# ESP-RC-Car.net
KiCad netlist of a schematic drawn in Altium Designer
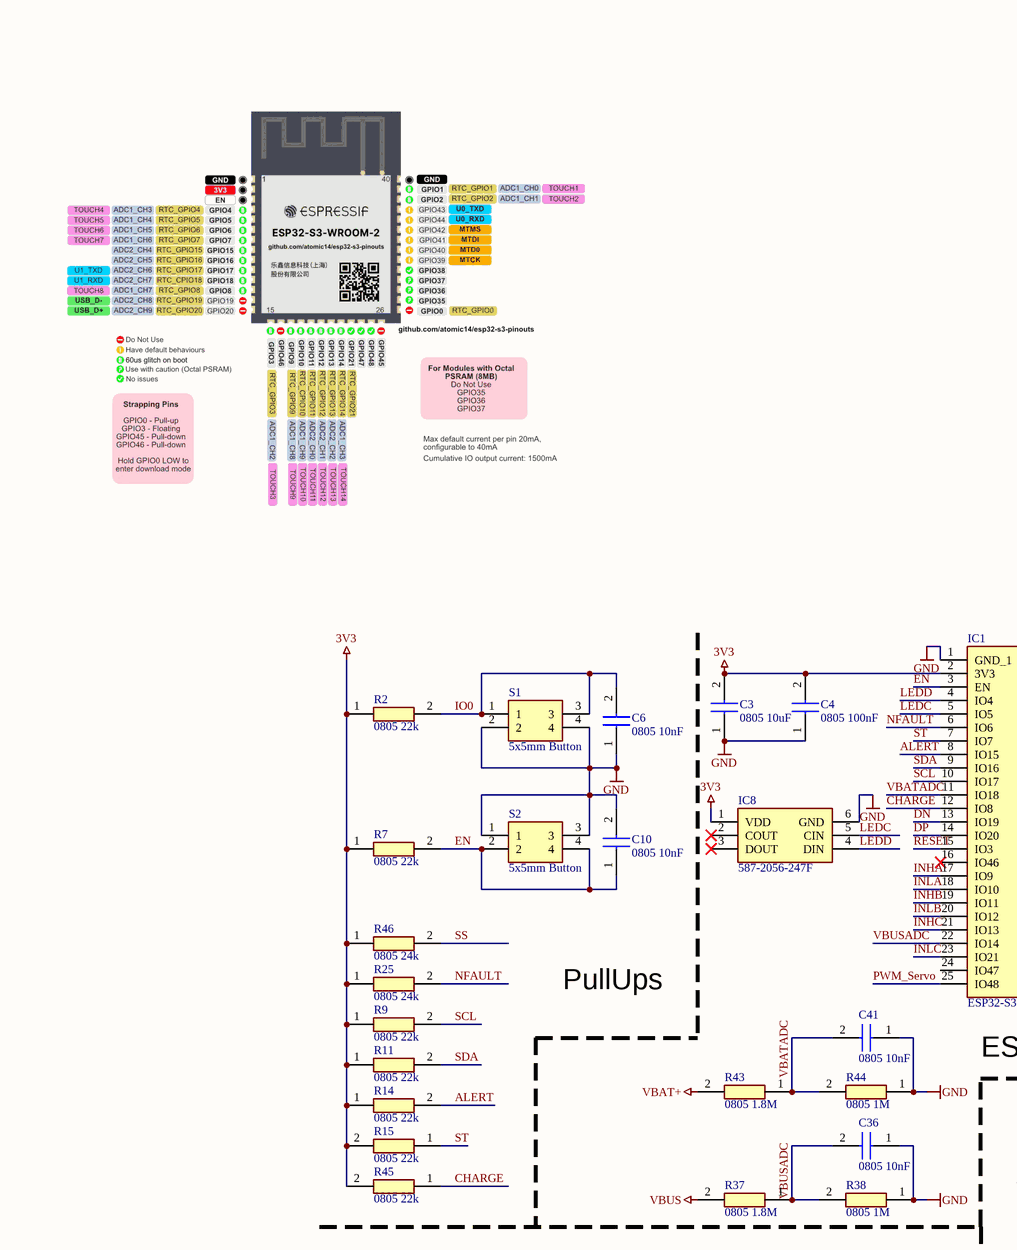
[diagram p0: ESP-RC-Car.SchDoc, top left]
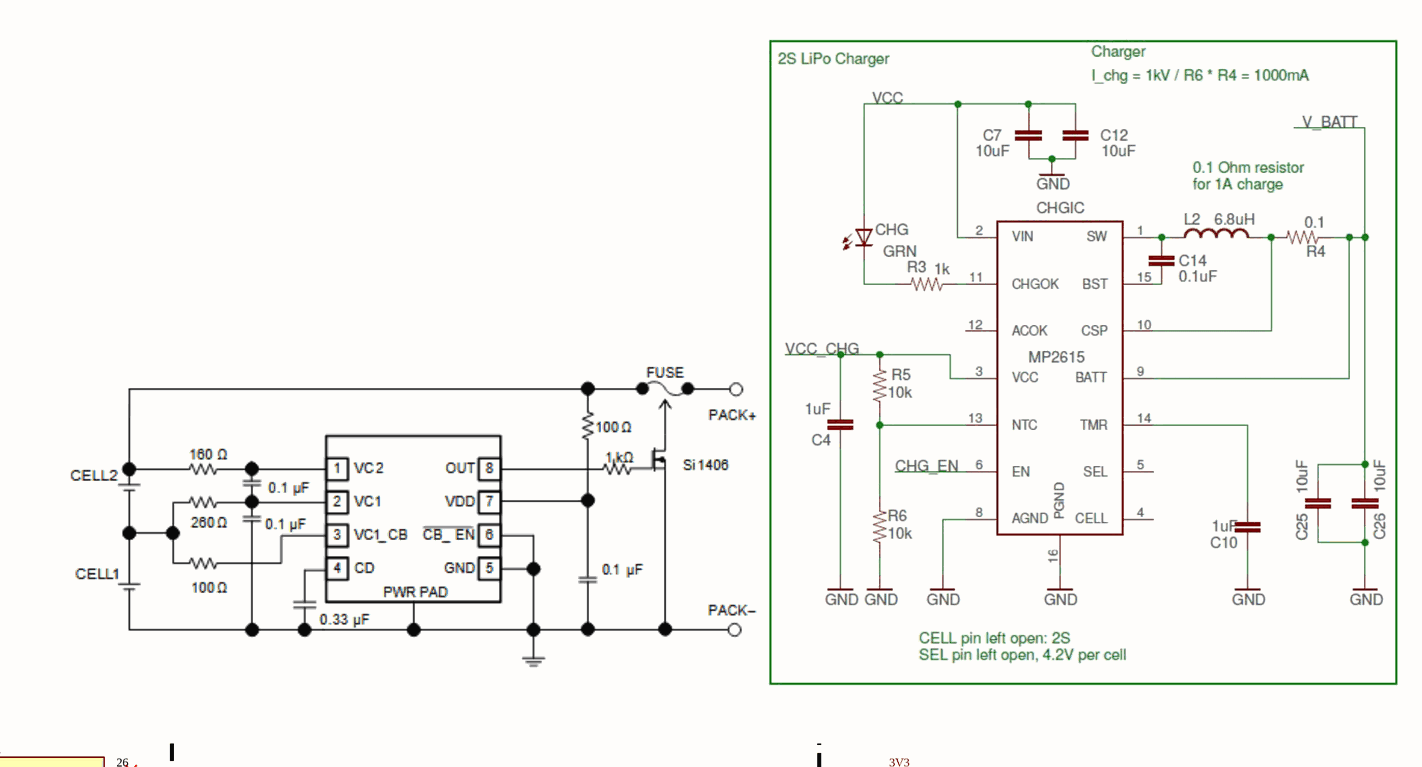
[diagram p1: ESP-RC-Car.SchDoc, top middle]
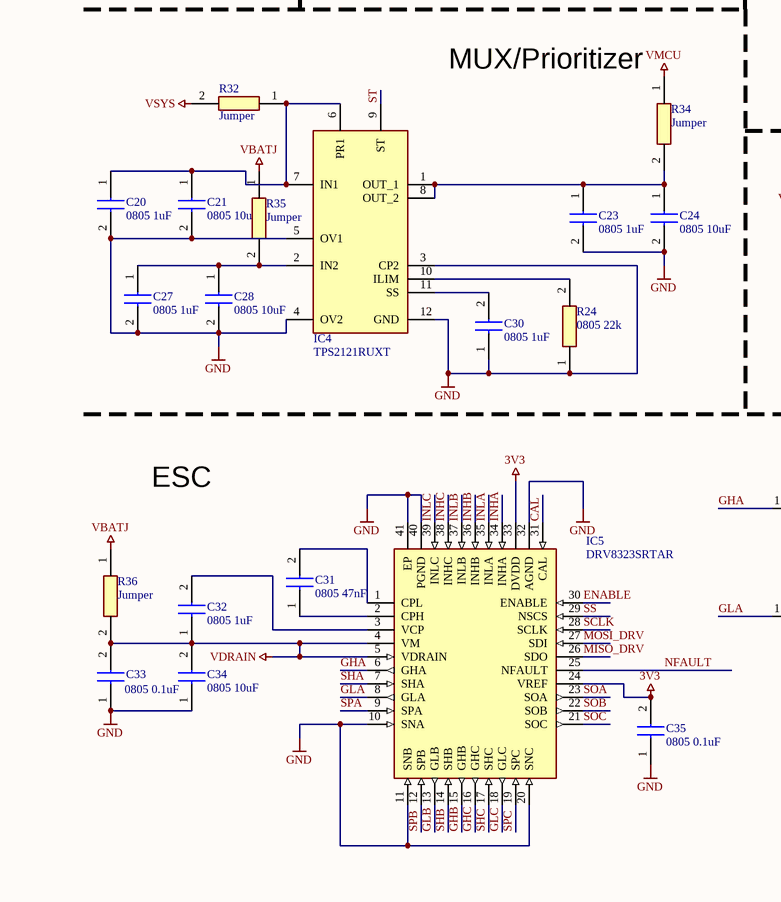
[diagram p2: ESP-RC-Car.SchDoc, bottom left]
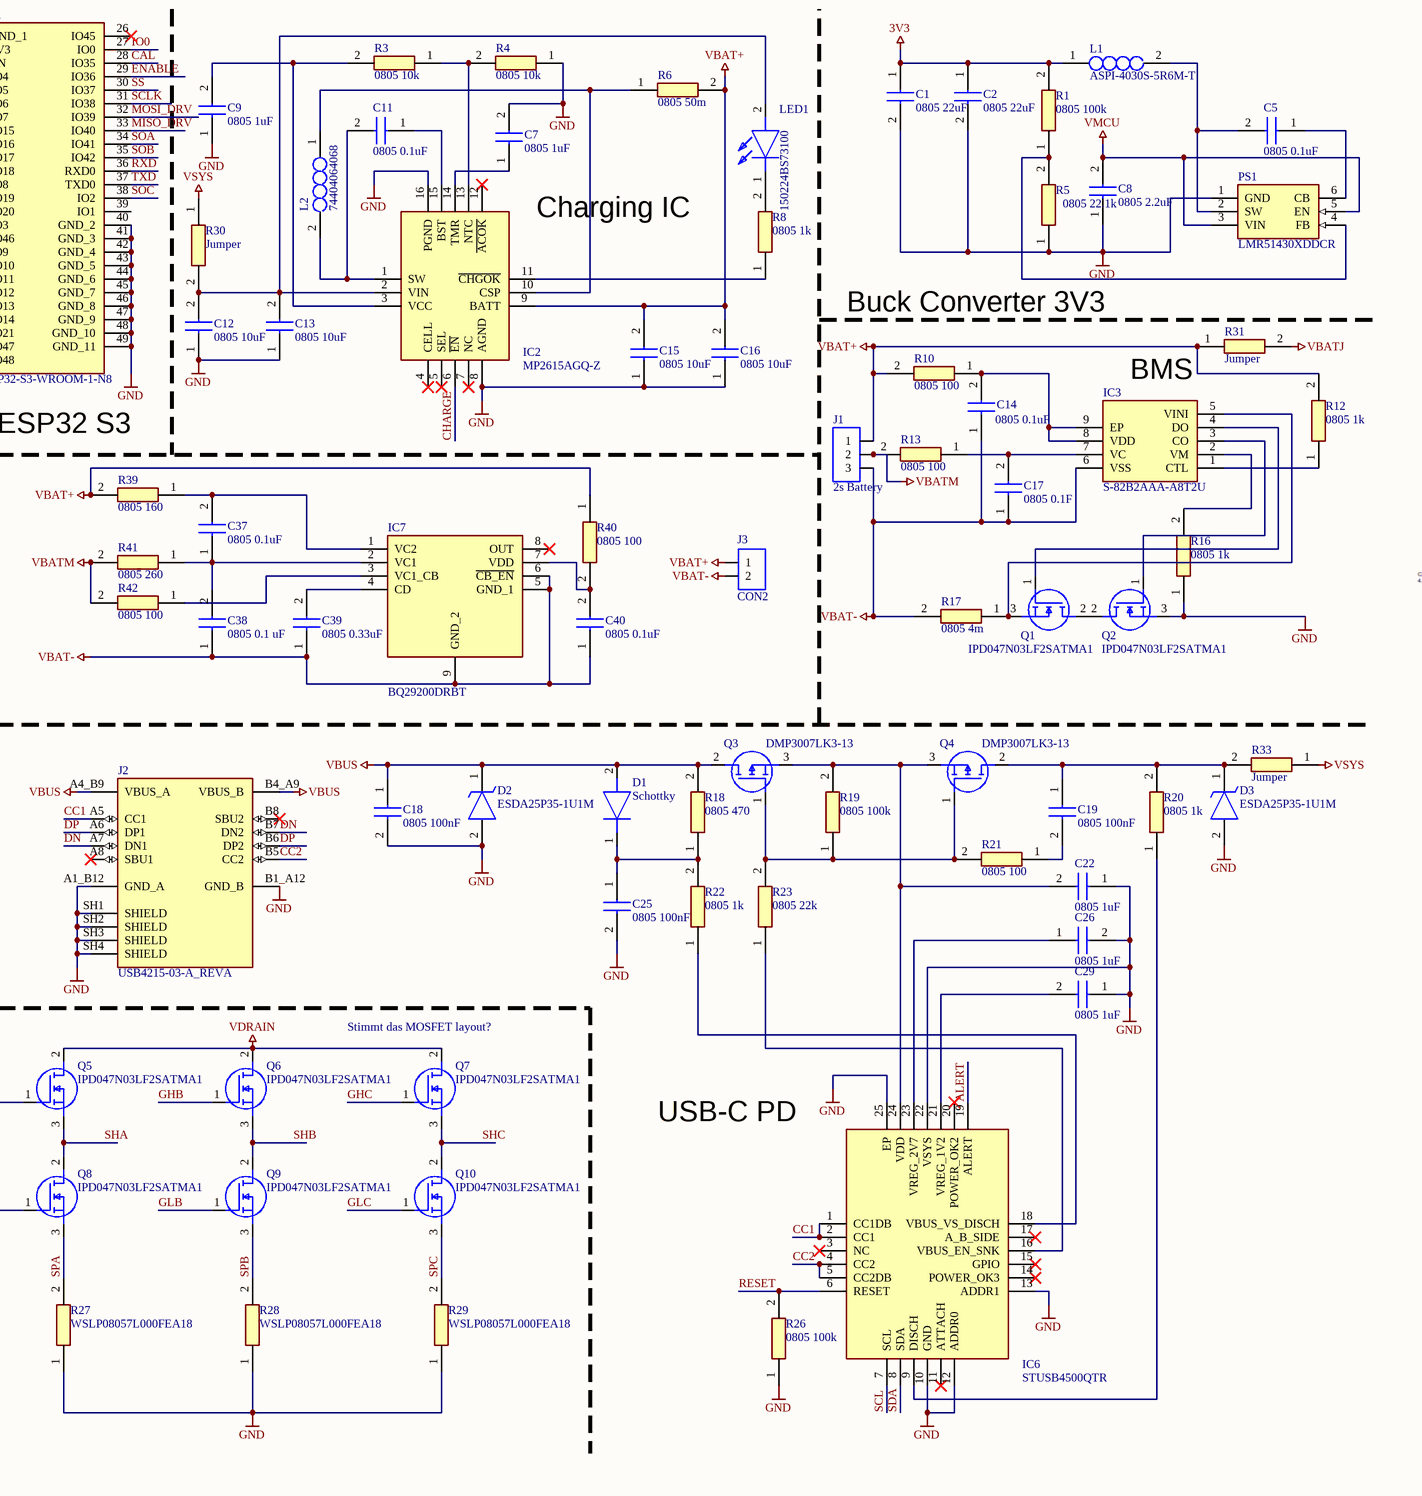
[diagram p3: ESP-RC-Car.SchDoc, bottom middle]
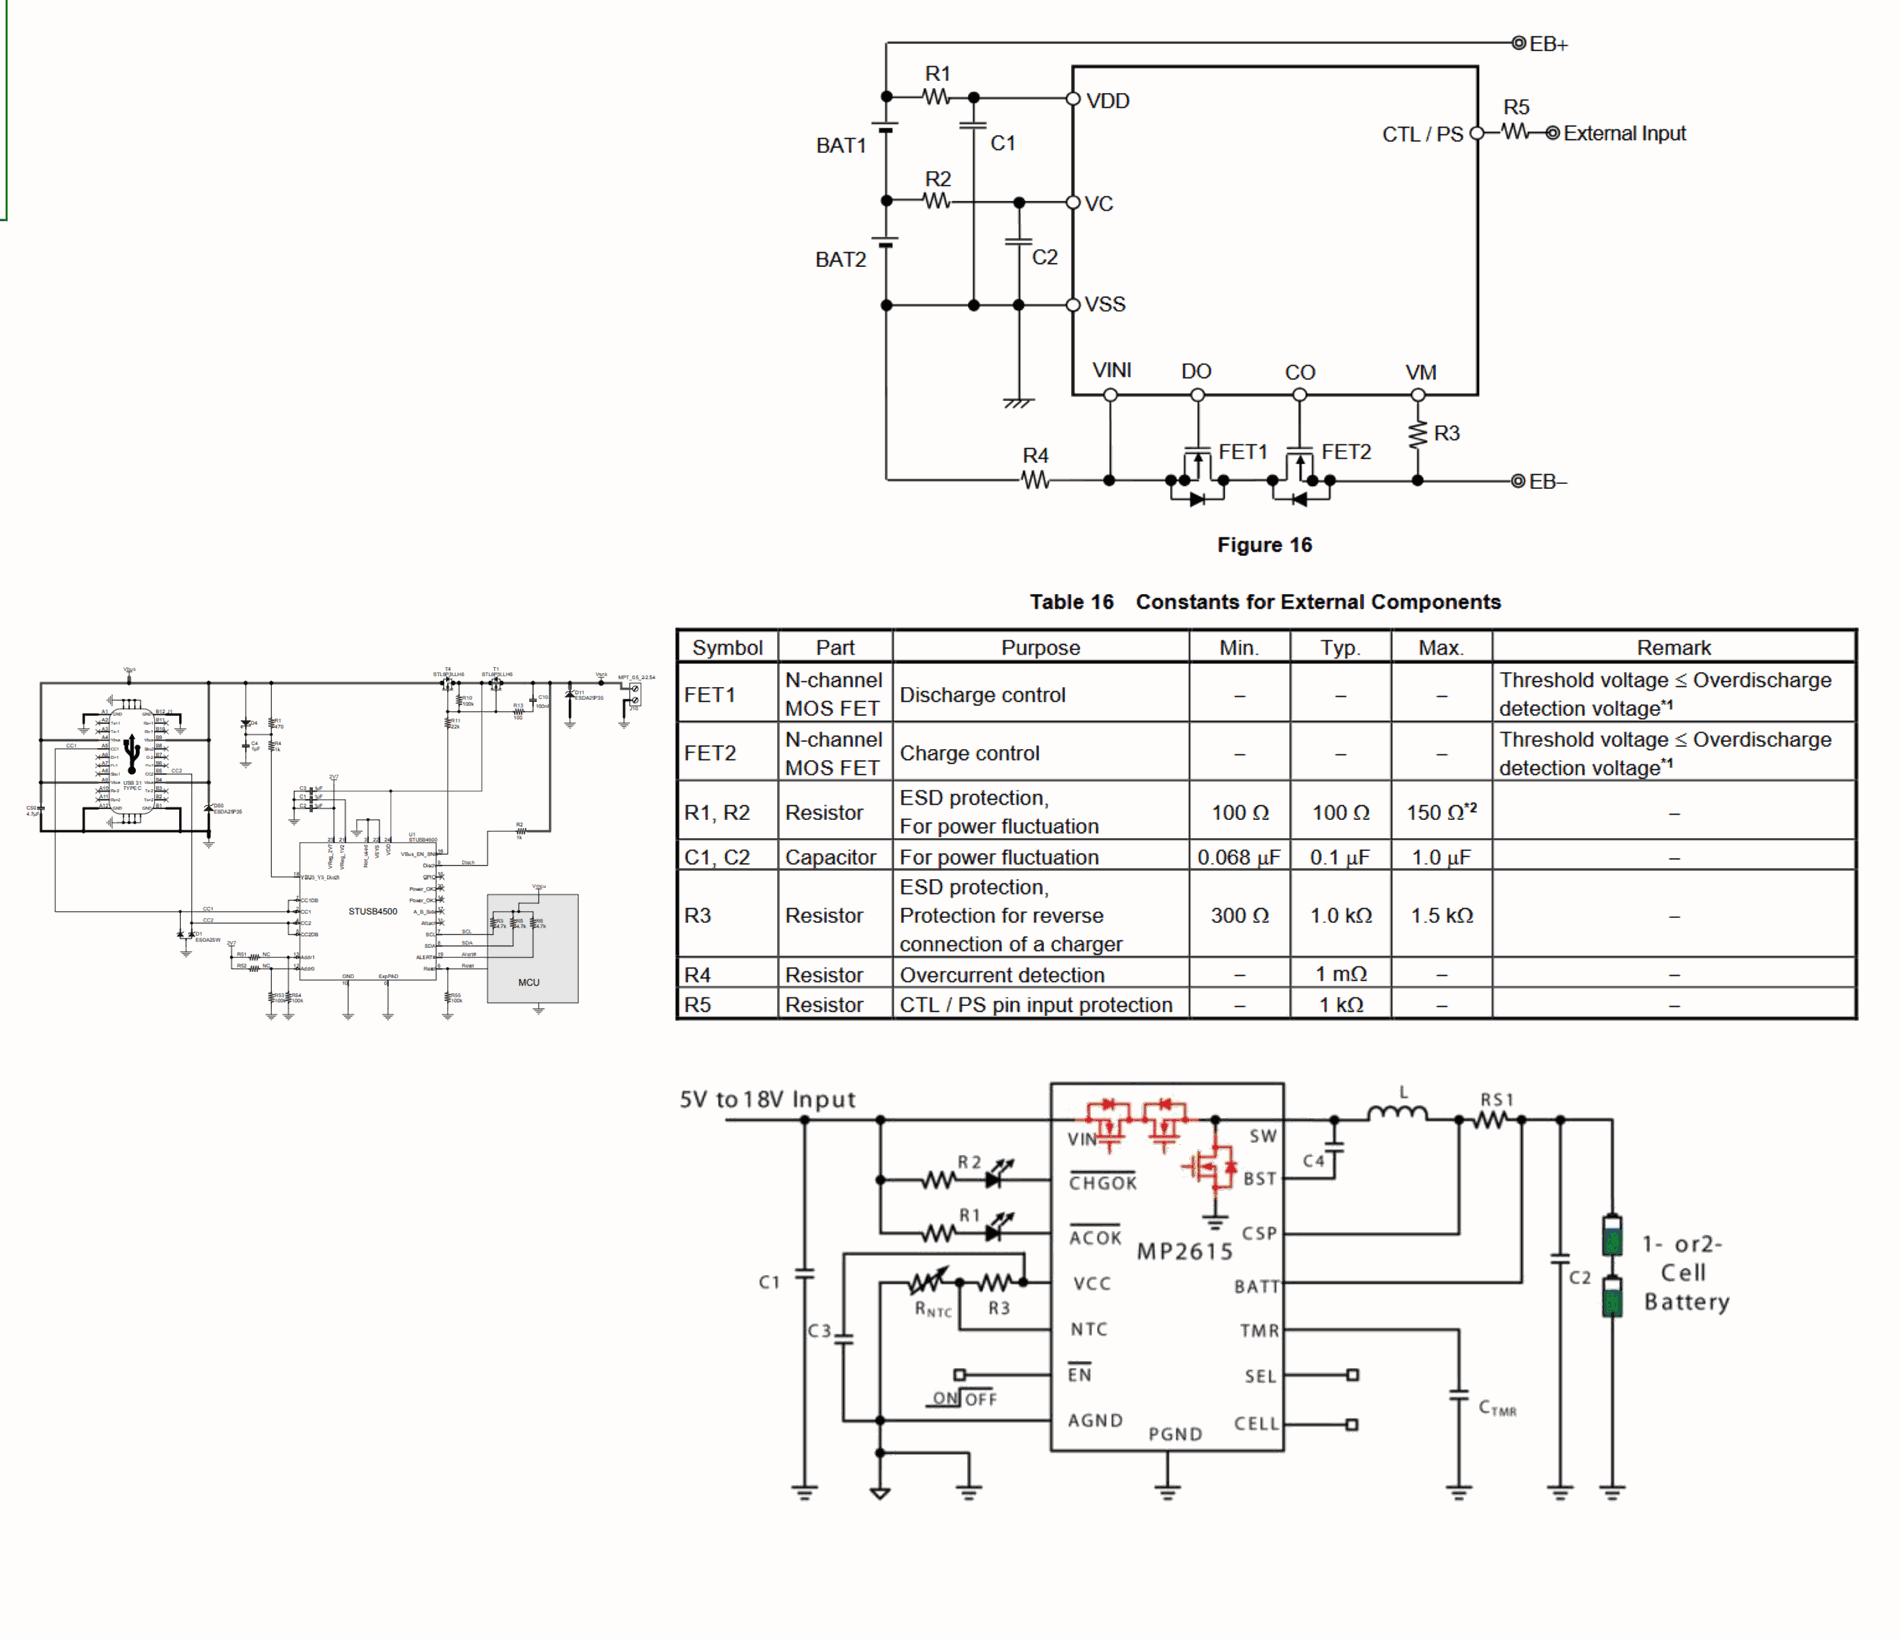
[diagram p4: ESP-RC-Car.SchDoc, bottom right]

(export (version "E")
  (design (tool "Eeschema 10.0.6"))
  (components
    (comp (ref "C1")
      (value "0805 22uF")
      (footprint "CAPC2012X94N")
      (description "Capacitor 25V")
      (fields
        (field (name "MANUFACTURER_PART_NUMBER") "08055A150JAT2A")
        (field (name "MOUSER PART NUMBER") "581-08055A150J")
      )
      (libsource (lib "*") (part "08055A150JAT2A"))
    )
    (comp (ref "C2")
      (value "0805 22uF")
      (footprint "CAPC2012X94N")
      (description "Capacitor 25V")
      (fields
        (field (name "MANUFACTURER_PART_NUMBER") "08055A150JAT2A")
        (field (name "MOUSER PART NUMBER") "581-08055A150J")
      )
      (libsource (lib "*") (part "08055A150JAT2A"))
    )
    (comp (ref "C3")
      (value "0805 10uF")
      (footprint "CAPC2012X94N")
      (description "Capacitor")
      (fields
        (field (name "MANUFACTURER_PART_NUMBER") "08055A150JAT2A")
        (field (name "MOUSER PART NUMBER") "581-08055A150J")
      )
      (libsource (lib "*") (part "08055A150JAT2A"))
    )
    (comp (ref "C4")
      (value "0805 100nF")
      (footprint "CAPC2012X94N")
      (description "Capacitor")
      (fields
        (field (name "MANUFACTURER_PART_NUMBER") "08055A150JAT2A")
        (field (name "MOUSER PART NUMBER") "581-08055A150J")
      )
      (libsource (lib "*") (part "08055A150JAT2A"))
    )
    (comp (ref "C5")
      (value "0805 0.1uF")
      (footprint "CAPC2012X94N")
      (description "Capacitor")
      (fields
        (field (name "MANUFACTURER_PART_NUMBER") "08055A150JAT2A")
        (field (name "MOUSER PART NUMBER") "581-08055A150J")
      )
      (libsource (lib "*") (part "08055A150JAT2A"))
    )
    (comp (ref "C6")
      (value "0805 10nF")
      (footprint "CAPC2012X94N")
      (description "Capacitor")
      (fields
        (field (name "MANUFACTURER_PART_NUMBER") "08055A150JAT2A")
        (field (name "MOUSER PART NUMBER") "581-08055A150J")
      )
      (libsource (lib "*") (part "08055A150JAT2A"))
    )
    (comp (ref "C7")
      (value "0805 1uF")
      (footprint "CAPC2012X94N")
      (description "Capacitor")
      (fields
        (field (name "MANUFACTURER_PART_NUMBER") "08055A150JAT2A")
        (field (name "MOUSER PART NUMBER") "581-08055A150J")
      )
      (libsource (lib "*") (part "08055A150JAT2A"))
    )
    (comp (ref "C8")
      (value "0805 2.2uF")
      (footprint "CAPC2012X94N")
      (description "Capacitor")
      (fields
        (field (name "MANUFACTURER_PART_NUMBER") "08055A150JAT2A")
        (field (name "MOUSER PART NUMBER") "581-08055A150J")
      )
      (libsource (lib "*") (part "08055A150JAT2A"))
    )
    (comp (ref "C9")
      (value "0805 1uF")
      (footprint "CAPC2012X94N")
      (description "Capacitor")
      (fields
        (field (name "MANUFACTURER_PART_NUMBER") "08055A150JAT2A")
        (field (name "MOUSER PART NUMBER") "581-08055A150J")
      )
      (libsource (lib "*") (part "08055A150JAT2A"))
    )
    (comp (ref "C10")
      (value "0805 10nF")
      (footprint "CAPC2012X94N")
      (description "Capacitor")
      (fields
        (field (name "MANUFACTURER_PART_NUMBER") "08055A150JAT2A")
        (field (name "MOUSER PART NUMBER") "581-08055A150J")
      )
      (libsource (lib "*") (part "08055A150JAT2A"))
    )
    (comp (ref "C11")
      (value "0805 0.1uF")
      (footprint "CAPC2012X94N")
      (description "Capacitor")
      (fields
        (field (name "MANUFACTURER_PART_NUMBER") "08055A150JAT2A")
        (field (name "MOUSER PART NUMBER") "581-08055A150J")
      )
      (libsource (lib "*") (part "08055A150JAT2A"))
    )
    (comp (ref "C12")
      (value "0805 10uF")
      (footprint "CAPC2012X94N")
      (description "Capacitor")
      (fields
        (field (name "MANUFACTURER_PART_NUMBER") "08055A150JAT2A")
        (field (name "MOUSER PART NUMBER") "581-08055A150J")
      )
      (libsource (lib "*") (part "08055A150JAT2A"))
    )
    (comp (ref "C13")
      (value "0805 10uF")
      (footprint "CAPC2012X94N")
      (description "Capacitor")
      (fields
        (field (name "MANUFACTURER_PART_NUMBER") "08055A150JAT2A")
        (field (name "MOUSER PART NUMBER") "581-08055A150J")
      )
      (libsource (lib "*") (part "08055A150JAT2A"))
    )
    (comp (ref "C14")
      (value "0805 0.1uF")
      (footprint "CAPC2012X94N")
      (description "Capacitor")
      (fields
        (field (name "MANUFACTURER_PART_NUMBER") "08055A150JAT2A")
        (field (name "MOUSER PART NUMBER") "581-08055A150J")
      )
      (libsource (lib "*") (part "08055A150JAT2A"))
    )
    (comp (ref "C15")
      (value "0805 10uF")
      (footprint "CAPC2012X94N")
      (description "Capacitor")
      (fields
        (field (name "MANUFACTURER_PART_NUMBER") "08055A150JAT2A")
        (field (name "MOUSER PART NUMBER") "581-08055A150J")
      )
      (libsource (lib "*") (part "08055A150JAT2A"))
    )
    (comp (ref "C16")
      (value "0805 10uF")
      (footprint "CAPC2012X94N")
      (description "Capacitor")
      (fields
        (field (name "MANUFACTURER_PART_NUMBER") "08055A150JAT2A")
        (field (name "MOUSER PART NUMBER") "581-08055A150J")
      )
      (libsource (lib "*") (part "08055A150JAT2A"))
    )
    (comp (ref "C17")
      (value "0805 0.1F")
      (footprint "CAPC2012X94N")
      (description "Capacitor")
      (fields
        (field (name "MANUFACTURER_PART_NUMBER") "08055A150JAT2A")
        (field (name "MOUSER PART NUMBER") "581-08055A150J")
      )
      (libsource (lib "*") (part "08055A150JAT2A"))
    )
    (comp (ref "C18")
      (value "0805 100nF")
      (footprint "CAPC2012X94N")
      (description "0805")
      (fields
        (field (name "MANUFACTURER_PART_NUMBER") "08055A150JAT2A")
        (field (name "MOUSER PART NUMBER") "581-08055A150J")
      )
      (libsource (lib "*") (part "08055A150JAT2A"))
    )
    (comp (ref "C19")
      (value "0805 100nF")
      (footprint "CAPC2012X94N")
      (description "0805")
      (fields
        (field (name "MANUFACTURER_PART_NUMBER") "08055A150JAT2A")
        (field (name "MOUSER PART NUMBER") "581-08055A150J")
      )
      (libsource (lib "*") (part "08055A150JAT2A"))
    )
    (comp (ref "C20")
      (value "0805 1uF")
      (footprint "CAPC2012X94N")
      (description "0805")
      (fields
        (field (name "MANUFACTURER_PART_NUMBER") "08055A150JAT2A")
        (field (name "MOUSER PART NUMBER") "581-08055A150J")
      )
      (libsource (lib "*") (part "08055A150JAT2A"))
    )
    (comp (ref "C21")
      (value "0805 10uF")
      (footprint "CAPC2012X94N")
      (description "0805")
      (fields
        (field (name "MANUFACTURER_PART_NUMBER") "08055A150JAT2A")
        (field (name "MOUSER PART NUMBER") "581-08055A150J")
      )
      (libsource (lib "*") (part "08055A150JAT2A"))
    )
    (comp (ref "C22")
      (value "0805 1uF")
      (footprint "CAPC2012X94N")
      (description "0805")
      (fields
        (field (name "MANUFACTURER_PART_NUMBER") "08055A150JAT2A")
        (field (name "MOUSER PART NUMBER") "581-08055A150J")
      )
      (libsource (lib "*") (part "08055A150JAT2A"))
    )
    (comp (ref "C23")
      (value "0805 1uF")
      (footprint "CAPC2012X94N")
      (description "0805")
      (fields
        (field (name "MANUFACTURER_PART_NUMBER") "08055A150JAT2A")
        (field (name "MOUSER PART NUMBER") "581-08055A150J")
      )
      (libsource (lib "*") (part "08055A150JAT2A"))
    )
    (comp (ref "C24")
      (value "0805 10uF")
      (footprint "CAPC2012X94N")
      (description "0805")
      (fields
        (field (name "MANUFACTURER_PART_NUMBER") "08055A150JAT2A")
        (field (name "MOUSER PART NUMBER") "581-08055A150J")
      )
      (libsource (lib "*") (part "08055A150JAT2A"))
    )
    (comp (ref "C25")
      (value "0805 100nF")
      (footprint "CAPC2012X94N")
      (description "0805")
      (fields
        (field (name "MANUFACTURER_PART_NUMBER") "08055A150JAT2A")
        (field (name "MOUSER PART NUMBER") "581-08055A150J")
      )
      (libsource (lib "*") (part "08055A150JAT2A"))
    )
    (comp (ref "C26")
      (value "0805 1uF")
      (footprint "CAPC2012X94N")
      (description "0805")
      (fields
        (field (name "MANUFACTURER_PART_NUMBER") "08055A150JAT2A")
        (field (name "MOUSER PART NUMBER") "581-08055A150J")
      )
      (libsource (lib "*") (part "08055A150JAT2A"))
    )
    (comp (ref "C27")
      (value "0805 1uF")
      (footprint "CAPC2012X94N")
      (description "0805")
      (fields
        (field (name "MANUFACTURER_PART_NUMBER") "08055A150JAT2A")
        (field (name "MOUSER PART NUMBER") "581-08055A150J")
      )
      (libsource (lib "*") (part "08055A150JAT2A"))
    )
    (comp (ref "C28")
      (value "0805 10uF")
      (footprint "CAPC2012X94N")
      (description "0805")
      (fields
        (field (name "MANUFACTURER_PART_NUMBER") "08055A150JAT2A")
        (field (name "MOUSER PART NUMBER") "581-08055A150J")
      )
      (libsource (lib "*") (part "08055A150JAT2A"))
    )
    (comp (ref "C29")
      (value "0805 1uF")
      (footprint "CAPC2012X94N")
      (description "0805")
      (fields
        (field (name "MANUFACTURER_PART_NUMBER") "08055A150JAT2A")
        (field (name "MOUSER PART NUMBER") "581-08055A150J")
      )
      (libsource (lib "*") (part "08055A150JAT2A"))
    )
    (comp (ref "C30")
      (value "0805 1uF")
      (footprint "CAPC2012X94N")
      (description "0805")
      (fields
        (field (name "MANUFACTURER_PART_NUMBER") "08055A150JAT2A")
        (field (name "MOUSER PART NUMBER") "581-08055A150J")
      )
      (libsource (lib "*") (part "08055A150JAT2A"))
    )
    (comp (ref "C31")
      (value "0805 47nF")
      (footprint "CAPC2012X94N")
      (description "0805")
      (fields
        (field (name "MANUFACTURER_PART_NUMBER") "08055A150JAT2A")
        (field (name "MOUSER PART NUMBER") "581-08055A150J")
      )
      (libsource (lib "*") (part "08055A150JAT2A"))
    )
    (comp (ref "C32")
      (value "0805 1uF")
      (footprint "CAPC2012X94N")
      (description "0805 16V X5R/X7R")
      (fields
        (field (name "MANUFACTURER_PART_NUMBER") "08055A150JAT2A")
        (field (name "MOUSER PART NUMBER") "581-08055A150J")
      )
      (libsource (lib "*") (part "08055A150JAT2A"))
    )
    (comp (ref "C33")
      (value "0805 0.1uF")
      (footprint "CAPC2012X94N")
      (description "0805 VM rated")
      (fields
        (field (name "MANUFACTURER_PART_NUMBER") "08055A150JAT2A")
        (field (name "MOUSER PART NUMBER") "581-08055A150J")
      )
      (libsource (lib "*") (part "08055A150JAT2A"))
    )
    (comp (ref "C34")
      (value "0805 10uF")
      (footprint "CAPC2012X94N")
      (description "0805")
      (fields
        (field (name "MANUFACTURER_PART_NUMBER") "08055A150JAT2A")
        (field (name "MOUSER PART NUMBER") "581-08055A150J")
      )
      (libsource (lib "*") (part "08055A150JAT2A"))
    )
    (comp (ref "C35")
      (value "0805 0.1uF")
      (footprint "CAPC2012X94N")
      (description "0805")
      (fields
        (field (name "MANUFACTURER_PART_NUMBER") "08055A150JAT2A")
        (field (name "MOUSER PART NUMBER") "581-08055A150J")
      )
      (libsource (lib "*") (part "08055A150JAT2A"))
    )
    (comp (ref "C36")
      (value "0805 10nF")
      (footprint "CAPC2012X94N")
      (description "Capacitor")
      (fields
        (field (name "MANUFACTURER_PART_NUMBER") "08055A150JAT2A")
        (field (name "MOUSER PART NUMBER") "581-08055A150J")
      )
      (libsource (lib "*") (part "08055A150JAT2A"))
    )
    (comp (ref "C37")
      (value "0805 0.1uF")
      (footprint "CAPC2012X94N")
      (description "Capacitor")
      (fields
        (field (name "MANUFACTURER_PART_NUMBER") "08055A150JAT2A")
        (field (name "MOUSER PART NUMBER") "581-08055A150J")
      )
      (libsource (lib "*") (part "08055A150JAT2A"))
    )
    (comp (ref "C38")
      (value "0805 0.1 uF")
      (footprint "CAPC2012X94N")
      (description "Capacitor")
      (fields
        (field (name "MANUFACTURER_PART_NUMBER") "08055A150JAT2A")
        (field (name "MOUSER PART NUMBER") "581-08055A150J")
      )
      (libsource (lib "*") (part "08055A150JAT2A"))
    )
    (comp (ref "C39")
      (value "0805 0.33uF")
      (footprint "CAPC2012X94N")
      (description "Capacitor")
      (fields
        (field (name "MANUFACTURER_PART_NUMBER") "08055A150JAT2A")
        (field (name "MOUSER PART NUMBER") "581-08055A150J")
      )
      (libsource (lib "*") (part "08055A150JAT2A"))
    )
    (comp (ref "C40")
      (value "0805 0.1uF")
      (footprint "CAPC2012X94N")
      (description "Capacitor")
      (fields
        (field (name "MANUFACTURER_PART_NUMBER") "08055A150JAT2A")
        (field (name "MOUSER PART NUMBER") "581-08055A150J")
      )
      (libsource (lib "*") (part "08055A150JAT2A"))
    )
    (comp (ref "C41")
      (value "0805 10nF")
      (footprint "CAPC2012X94N")
      (description "Capacitor")
      (fields
        (field (name "MANUFACTURER_PART_NUMBER") "08055A150JAT2A")
        (field (name "MOUSER PART NUMBER") "581-08055A150J")
      )
      (libsource (lib "*") (part "08055A150JAT2A"))
    )
    (comp (ref "D1")
      (value "Schottky")
      (footprint "SODFL3517X110N")
      (description "Schottky Diode")
      (fields (field (name "MANUFACTURER_PART_NUMBER") "PMEG3010ER"))
      (libsource (lib "*") (part "PMEG3010ER"))
    )
    (comp (ref "D2")
      (value "ESDA25P35-1U1M")
      (footprint "ESDA25P351U1M")
      (description "TVS Diode (Uni-directional)")
      (fields (field (name "MOUSER PART NUMBER") "511-ESDA25P35-1U1M"))
      (libsource (lib "*") (part "ESDA25P35-1U1M"))
    )
    (comp (ref "D3")
      (value "ESDA25P35-1U1M")
      (footprint "ESDA25P351U1M")
      (description "TVS Diode (Uni-directional)")
      (fields (field (name "MOUSER PART NUMBER") "511-ESDA25P35-1U1M"))
      (libsource (lib "*") (part "ESDA25P35-1U1M"))
    )
    (comp (ref "IC1")
      (value "ESP32-S3-WROOM-1-N8")
      (footprint "ESP32S3WROOM1N8R2")
      (description "Integrated Circuit")
      (fields (field (name "MOUSER PART NUMBER") "356-ESP32-S3WROOM1N8"))
      (libsource (lib "*") (part "ESP32-S3-WROOM-1-N8"))
    )
    (comp (ref "IC2")
      (value "MP2615AGQ-Z")
      (footprint "MP2615AGQZ")
      (description "Integrated Circuit")
      (fields (field (name "MOUSER PART NUMBER") "946-MP2615AGQ-Z"))
      (libsource (lib "*") (part "MP2615AGQ-Z"))
    )
    (comp (ref "IC3")
      (value "S-82B2AAA-A8T2U")
      (footprint "S82B2AAAA8T2U")
      (description "Integrated Circuit")
      (fields (field (name "MOUSER PART NUMBER") "628-S-82B2AAA-A8T2U"))
      (libsource (lib "*") (part "S-82B2AAA-A8T2U"))
    )
    (comp (ref "IC4")
      (value "TPS2121RUXT")
      (footprint "TPS2121RUXT")
      (description "Integrated Circuit")
      (fields (field (name "MOUSER PART NUMBER") "595-TPS2121RUXT"))
      (libsource (lib "*") (part "TPS2121RUXT"))
    )
    (comp (ref "IC5")
      (value "DRV8323SRTAR")
      (footprint "QFN50P600X600X80-41N-D")
      (description "Integrated Circuit")
      (fields (field (name "MOUSER PART NUMBER") "595-DRV8323SRTAR"))
      (libsource (lib "lib") (part "DRV8323SRTAR"))
    )
    (comp (ref "IC6")
      (value "STUSB4500QTR")
      (footprint "QFN50P400X400X100-25N-D")
      (description "Integrated Circuit")
      (fields (field (name "MOUSER PART NUMBER") "511-STUSB4500QTR"))
      (libsource (lib "*") (part "STUSB4500QTR"))
    )
    (comp (ref "IC7")
      (value "BQ29200DRBT")
      (footprint "SON65P300X300X100-9N-D")
      (description "Integrated Circuit")
      (fields (field (name "MOUSER PART NUMBER") "595-BQ29200DRBT"))
      (libsource (lib "*") (part "BQ29200DRBT"))
    )
    (comp (ref "IC8")
      (value "587-2056-247F")
      (footprint "lib:5872056247F")
      (description "Integrated Circuit")
      (libsource (lib "*") (part "587-2056-247F"))
    )
    (comp (ref "J1")
      (value "2s Battery")
      (footprint "Sip-3")
      (description "Stecker")
      (libsource (lib "lib") (part "CON3"))
    )
    (comp (ref "J2")
      (value "USB4215-03-A_REVA")
      (footprint "GCT_USB4215-03-A_REVA")
      (fields (field (name "MF") "Global Connector Technology") (field (name "MP") "USB4215-03-A"))
      (libsource (lib "lib") (part "USB4215-03-A_REVA"))
    )
    (comp (ref "J3")
      (value "CON2")
      (footprint "SIP-2")
      (description "Stecker")
      (libsource (lib "lib") (part "CON2"))
    )
    (comp (ref "L1")
      (value "ASPI-4030S-5R6M-T")
      (footprint "ASPI-4030S")
      (description "Inductor")
      (fields (field (name "MOUSER PART NUMBER") "815-ASPI-4030S-5R6MT"))
      (libsource (lib "*") (part "ASPI-4030S-5R6M-T"))
    )
    (comp (ref "L2")
      (value "74404064068")
      (footprint "INDPM6060X450N")
      (description "Inductor")
      (fields (field (name "MOUSER PART NUMBER") "710-74404064068"))
      (libsource (lib "*") (part "74404064068"))
    )
    (comp (ref "LED1")
      (value "150224BS73100")
      (footprint "150224BS73100")
      (description "LED")
      (fields (field (name "MOUSER PART NUMBER") "710-150224BS73100"))
      (libsource (lib "*") (part "150224BS73100"))
    )
    (comp (ref "PS1")
      (value "LMR51430XDDCR")
      (footprint "SOT95P280X110-6N")
      (description "Power Supply 500kHz")
      (fields (field (name "MOUSER PART NUMBER") "595-LMR51430XDDCR"))
      (libsource (lib "*") (part "LMR51430XDDCR"))
    )
    (comp (ref "Q1")
      (value "IPD047N03LF2SATMA1")
      (footprint "IPD047N03LF2SATMA1")
      (description "MOSFET (N-Channel)")
      (fields (field (name "MOUSER PART NUMBER") "726-IPD047N03LF2SATM"))
      (libsource (lib "*") (part "IPD047N03LF2SATMA1"))
    )
    (comp (ref "Q2")
      (value "IPD047N03LF2SATMA1")
      (footprint "IPD047N03LF2SATMA1")
      (description "MOSFET (N-Channel)")
      (fields (field (name "MOUSER PART NUMBER") "726-IPD047N03LF2SATM"))
      (libsource (lib "*") (part "IPD047N03LF2SATMA1"))
    )
    (comp (ref "Q3")
      (value "DMP3007LK3-13")
      (footprint "DMP3007LK313")
      (description "MOSFET (P-Channel)")
      (fields (field (name "MOUSER PART NUMBER") "621-DMP3007LK3-13"))
      (libsource (lib "*") (part "DMP3007LK3-13"))
    )
    (comp (ref "Q4")
      (value "DMP3007LK3-13")
      (footprint "DMP3007LK313")
      (description "MOSFET (P-Channel)")
      (fields (field (name "MOUSER PART NUMBER") "621-DMP3007LK3-13"))
      (libsource (lib "*") (part "DMP3007LK3-13"))
    )
    (comp (ref "Q5")
      (value "IPD047N03LF2SATMA1")
      (footprint "IPD047N03LF2SATMA1")
      (description "MOSFET (N-Channel)")
      (fields (field (name "MOUSER PART NUMBER") "726-IPD047N03LF2SATM"))
      (libsource (lib "*") (part "IPD047N03LF2SATMA1"))
    )
    (comp (ref "Q6")
      (value "IPD047N03LF2SATMA1")
      (footprint "IPD047N03LF2SATMA1")
      (description "MOSFET (N-Channel)")
      (fields (field (name "MOUSER PART NUMBER") "726-IPD047N03LF2SATM"))
      (libsource (lib "*") (part "IPD047N03LF2SATMA1"))
    )
    (comp (ref "Q7")
      (value "IPD047N03LF2SATMA1")
      (footprint "IPD047N03LF2SATMA1")
      (description "MOSFET (N-Channel)")
      (fields (field (name "MOUSER PART NUMBER") "726-IPD047N03LF2SATM"))
      (libsource (lib "*") (part "IPD047N03LF2SATMA1"))
    )
    (comp (ref "Q8")
      (value "IPD047N03LF2SATMA1")
      (footprint "IPD047N03LF2SATMA1")
      (description "MOSFET (N-Channel)")
      (fields (field (name "MOUSER PART NUMBER") "726-IPD047N03LF2SATM"))
      (libsource (lib "*") (part "IPD047N03LF2SATMA1"))
    )
    (comp (ref "Q9")
      (value "IPD047N03LF2SATMA1")
      (footprint "IPD047N03LF2SATMA1")
      (description "MOSFET (N-Channel)")
      (fields (field (name "MOUSER PART NUMBER") "726-IPD047N03LF2SATM"))
      (libsource (lib "*") (part "IPD047N03LF2SATMA1"))
    )
    (comp (ref "Q10")
      (value "IPD047N03LF2SATMA1")
      (footprint "IPD047N03LF2SATMA1")
      (description "MOSFET (N-Channel)")
      (fields (field (name "MOUSER PART NUMBER") "726-IPD047N03LF2SATM"))
      (libsource (lib "*") (part "IPD047N03LF2SATMA1"))
    )
    (comp (ref "R1")
      (value "0805 100k")
      (footprint "RESC2012X65N")
      (description "Resistor low tolerance")
      (fields (field (name "MANUFACTURER_PART_NUMBER") "CPF0805B102RE1"))
      (libsource (lib "") (part "CPF0805B102RE1_2"))
    )
    (comp (ref "R2")
      (value "0805 22k")
      (footprint "RESC2012X65N")
      (description "Resistor")
      (fields (field (name "MANUFACTURER_PART_NUMBER") "CPF0805B102RE1"))
      (libsource (lib "*") (part "CPF0805B102RE1"))
    )
    (comp (ref "R3")
      (value "0805 10k")
      (footprint "RESC2012X65N")
      (description "Resistor low tolerance")
      (fields (field (name "MANUFACTURER_PART_NUMBER") "CPF0805B102RE1"))
      (libsource (lib "") (part "CPF0805B102RE1_1"))
    )
    (comp (ref "R4")
      (value "0805 10k")
      (footprint "RESC2012X65N")
      (description "Resistor low tolerance")
      (fields (field (name "MANUFACTURER_PART_NUMBER") "CPF0805B102RE1"))
      (libsource (lib "") (part "CPF0805B102RE1_1"))
    )
    (comp (ref "R5")
      (value "0805 22.1k")
      (footprint "RESC2012X65N")
      (description "Resistor low tolerance")
      (fields (field (name "MANUFACTURER_PART_NUMBER") "CPF0805B102RE1"))
      (libsource (lib "") (part "CPF0805B102RE1_2"))
    )
    (comp (ref "R6")
      (value "0805 50m")
      (footprint "RESC2012X65N")
      (description "Resistor low tolerance")
      (fields (field (name "MANUFACTURER_PART_NUMBER") "CPF0805B102RE1"))
      (libsource (lib "*") (part "CPF0805B102RE1"))
    )
    (comp (ref "R7")
      (value "0805 22k")
      (footprint "RESC2012X65N")
      (description "Resistor")
      (fields (field (name "MANUFACTURER_PART_NUMBER") "CPF0805B102RE1"))
      (libsource (lib "*") (part "CPF0805B102RE1"))
    )
    (comp (ref "R8")
      (value "0805 1k")
      (footprint "RESC2012X65N")
      (description "Resistor low tolerance")
      (fields (field (name "MANUFACTURER_PART_NUMBER") "CPF0805B102RE1"))
      (libsource (lib "") (part "CPF0805B102RE1_2"))
    )
    (comp (ref "R9")
      (value "0805 22k")
      (footprint "RESC2012X65N")
      (description "Resistor")
      (fields (field (name "MANUFACTURER_PART_NUMBER") "CPF0805B102RE1"))
      (libsource (lib "*") (part "CPF0805B102RE1"))
    )
    (comp (ref "R10")
      (value "0805 100")
      (footprint "RESC2012X65N")
      (description "Resistor low tolerance")
      (fields (field (name "MANUFACTURER_PART_NUMBER") "CPF0805B102RE1"))
      (libsource (lib "") (part "CPF0805B102RE1_1"))
    )
    (comp (ref "R11")
      (value "0805 22k")
      (footprint "RESC2012X65N")
      (description "Resistor")
      (fields (field (name "MANUFACTURER_PART_NUMBER") "CPF0805B102RE1"))
      (libsource (lib "*") (part "CPF0805B102RE1"))
    )
    (comp (ref "R12")
      (value "0805 1k")
      (footprint "RESC2012X65N")
      (description "Resistor low tolerance")
      (fields (field (name "MANUFACTURER_PART_NUMBER") "CPF0805B102RE1"))
      (libsource (lib "") (part "CPF0805B102RE1_2"))
    )
    (comp (ref "R13")
      (value "0805 100")
      (footprint "RESC2012X65N")
      (description "Resistor low tolerance")
      (fields (field (name "MANUFACTURER_PART_NUMBER") "CPF0805B102RE1"))
      (libsource (lib "") (part "CPF0805B102RE1_1"))
    )
    (comp (ref "R14")
      (value "0805 22k")
      (footprint "RESC2012X65N")
      (description "Resistor")
      (fields (field (name "MANUFACTURER_PART_NUMBER") "CPF0805B102RE1"))
      (libsource (lib "*") (part "CPF0805B102RE1"))
    )
    (comp (ref "R15")
      (value "0805 22k")
      (footprint "RESC2012X65N")
      (description "Resistor")
      (fields (field (name "MANUFACTURER_PART_NUMBER") "CPF0805B102RE1"))
      (libsource (lib "") (part "CPF0805B102RE1_1"))
    )
    (comp (ref "R16")
      (value "0805 1k")
      (footprint "RESC2012X65N")
      (description "Resistor low tolerance")
      (fields (field (name "MANUFACTURER_PART_NUMBER") "CPF0805B102RE1"))
      (libsource (lib "") (part "CPF0805B102RE1_2"))
    )
    (comp (ref "R17")
      (value "0805 4m")
      (footprint "RESC2012X65N")
      (description "Resistor low tolerance")
      (fields (field (name "MANUFACTURER_PART_NUMBER") "CPF0805B102RE1"))
      (libsource (lib "") (part "CPF0805B102RE1_1"))
    )
    (comp (ref "R18")
      (value "0805 470")
      (footprint "RESC2012X65N")
      (description "Resistor")
      (fields (field (name "MANUFACTURER_PART_NUMBER") "CPF0805B102RE1"))
      (libsource (lib "") (part "CPF0805B102RE1_2"))
    )
    (comp (ref "R19")
      (value "0805 100k")
      (footprint "RESC2012X65N")
      (description "Resistor")
      (fields (field (name "MANUFACTURER_PART_NUMBER") "CPF0805B102RE1"))
      (libsource (lib "") (part "CPF0805B102RE1_2"))
    )
    (comp (ref "R20")
      (value "0805 1k")
      (footprint "RESC2012X65N")
      (description "Resistor")
      (fields (field (name "MANUFACTURER_PART_NUMBER") "CPF0805B102RE1"))
      (libsource (lib "") (part "CPF0805B102RE1_2"))
    )
    (comp (ref "R21")
      (value "0805 100")
      (footprint "RESC2012X65N")
      (description "Resistor")
      (fields (field (name "MANUFACTURER_PART_NUMBER") "CPF0805B102RE1"))
      (libsource (lib "") (part "CPF0805B102RE1_1"))
    )
    (comp (ref "R22")
      (value "0805 1k")
      (footprint "RESC2012X65N")
      (description "Resistor")
      (fields (field (name "MANUFACTURER_PART_NUMBER") "CPF0805B102RE1"))
      (libsource (lib "") (part "CPF0805B102RE1_2"))
    )
    (comp (ref "R23")
      (value "0805 22k")
      (footprint "RESC2012X65N")
      (description "Resistor")
      (fields (field (name "MANUFACTURER_PART_NUMBER") "CPF0805B102RE1"))
      (libsource (lib "") (part "CPF0805B102RE1_2"))
    )
    (comp (ref "R24")
      (value "0805 22k")
      (footprint "RESC2012X65N")
      (description "Resistor")
      (fields (field (name "MANUFACTURER_PART_NUMBER") "CPF0805B102RE1"))
      (libsource (lib "") (part "CPF0805B102RE1_2"))
    )
    (comp (ref "R25")
      (value "0805 24k")
      (footprint "RESC2012X65N")
      (description "Resistor")
      (fields (field (name "MANUFACTURER_PART_NUMBER") "CPF0805B102RE1"))
      (libsource (lib "*") (part "CPF0805B102RE1"))
    )
    (comp (ref "R26")
      (value "0805 100k")
      (footprint "RESC2012X65N")
      (description "Resistor")
      (fields (field (name "MANUFACTURER_PART_NUMBER") "CPF0805B102RE1"))
      (libsource (lib "") (part "CPF0805B102RE1_2"))
    )
    (comp (ref "R27")
      (value "WSLP08057L000FEA18")
      (footprint "RESC2013X58N")
      (description "Resistor")
      (fields (field (name "MOUSER PART NUMBER") "71-WSLP08057L000FEA1"))
      (libsource (lib "*") (part "WSLP08057L000FEA18"))
    )
    (comp (ref "R28")
      (value "WSLP08057L000FEA18")
      (footprint "RESC2013X58N")
      (description "Resistor")
      (fields (field (name "MOUSER PART NUMBER") "71-WSLP08057L000FEA1"))
      (libsource (lib "*") (part "WSLP08057L000FEA18"))
    )
    (comp (ref "R29")
      (value "WSLP08057L000FEA18")
      (footprint "RESC2013X58N")
      (description "Resistor")
      (fields (field (name "MOUSER PART NUMBER") "71-WSLP08057L000FEA1"))
      (libsource (lib "*") (part "WSLP08057L000FEA18"))
    )
    (comp (ref "R30")
      (value "Jumper")
      (footprint "Solder Jumper 5A")
      (description "Resistor")
      (fields (field (name "MANUFACTURER_PART_NUMBER") "CPF0805B102RE1"))
      (libsource (lib "") (part "CPF0805B102RE1_3"))
    )
    (comp (ref "R31")
      (value "Jumper")
      (footprint "Solder Jumper 9A")
      (description "Resistor")
      (fields (field (name "MANUFACTURER_PART_NUMBER") "CPF0805B102RE1"))
      (libsource (lib "*") (part "CPF0805B102RE1"))
    )
    (comp (ref "R32")
      (value "Jumper")
      (footprint "Solder Jumper 5A")
      (description "Resistor")
      (fields (field (name "MANUFACTURER_PART_NUMBER") "CPF0805B102RE1"))
      (libsource (lib "") (part "CPF0805B102RE1_1"))
    )
    (comp (ref "R33")
      (value "Jumper")
      (footprint "Solder Jumper 5A")
      (description "Resistor")
      (fields (field (name "MANUFACTURER_PART_NUMBER") "CPF0805B102RE1"))
      (libsource (lib "") (part "CPF0805B102RE1_1"))
    )
    (comp (ref "R34")
      (value "Jumper")
      (footprint "Solder Jumper 5A")
      (description "Resistor")
      (fields (field (name "MANUFACTURER_PART_NUMBER") "CPF0805B102RE1"))
      (libsource (lib "") (part "CPF0805B102RE1_3"))
    )
    (comp (ref "R35")
      (value "Jumper")
      (footprint "Solder Jumper 5A")
      (description "Resistor")
      (fields (field (name "MANUFACTURER_PART_NUMBER") "CPF0805B102RE1"))
      (libsource (lib "") (part "CPF0805B102RE1_3"))
    )
    (comp (ref "R36")
      (value "Jumper")
      (footprint "Solder Jumper 9A")
      (description "Resistor")
      (fields (field (name "MANUFACTURER_PART_NUMBER") "CPF0805B102RE1"))
      (libsource (lib "") (part "CPF0805B102RE1_3"))
    )
    (comp (ref "R37")
      (value "0805 1.8M")
      (footprint "RESC2012X65N")
      (description "Resistor")
      (fields (field (name "MANUFACTURER_PART_NUMBER") "CPF0805B102RE1"))
      (libsource (lib "") (part "CPF0805B102RE1_1"))
    )
    (comp (ref "R38")
      (value "0805 1M")
      (footprint "RESC2012X65N")
      (description "Resistor")
      (fields (field (name "MANUFACTURER_PART_NUMBER") "CPF0805B102RE1"))
      (libsource (lib "") (part "CPF0805B102RE1_1"))
    )
    (comp (ref "R39")
      (value "0805 160")
      (footprint "RESC2012X65N")
      (description "Resistor low tolerance")
      (fields (field (name "MANUFACTURER_PART_NUMBER") "CPF0805B102RE1"))
      (libsource (lib "") (part "CPF0805B102RE1_1"))
    )
    (comp (ref "R40")
      (value "0805 100")
      (footprint "RESC2012X65N")
      (description "Resistor low tolerance")
      (fields (field (name "MANUFACTURER_PART_NUMBER") "CPF0805B102RE1"))
      (libsource (lib "") (part "CPF0805B102RE1_3"))
    )
    (comp (ref "R41")
      (value "0805 260")
      (footprint "RESC2012X65N")
      (description "Resistor low tolerance")
      (fields (field (name "MANUFACTURER_PART_NUMBER") "CPF0805B102RE1"))
      (libsource (lib "") (part "CPF0805B102RE1_1"))
    )
    (comp (ref "R42")
      (value "0805 100")
      (footprint "RESC2012X65N")
      (description "Resistor low tolerance")
      (fields (field (name "MANUFACTURER_PART_NUMBER") "CPF0805B102RE1"))
      (libsource (lib "") (part "CPF0805B102RE1_1"))
    )
    (comp (ref "R43")
      (value "0805 1.8M")
      (footprint "RESC2012X65N")
      (description "Resistor")
      (fields (field (name "MANUFACTURER_PART_NUMBER") "CPF0805B102RE1"))
      (libsource (lib "") (part "CPF0805B102RE1_1"))
    )
    (comp (ref "R44")
      (value "0805 1M")
      (footprint "RESC2012X65N")
      (description "Resistor")
      (fields (field (name "MANUFACTURER_PART_NUMBER") "CPF0805B102RE1"))
      (libsource (lib "") (part "CPF0805B102RE1_1"))
    )
    (comp (ref "R45")
      (value "0805 22k")
      (footprint "RESC2012X65N")
      (description "Resistor")
      (fields (field (name "MANUFACTURER_PART_NUMBER") "CPF0805B102RE1"))
      (libsource (lib "") (part "CPF0805B102RE1_1"))
    )
    (comp (ref "R46")
      (value "0805 24k")
      (footprint "RESC2012X65N")
      (description "Resistor")
      (fields (field (name "MANUFACTURER_PART_NUMBER") "CPF0805B102RE1"))
      (libsource (lib "*") (part "CPF0805B102RE1"))
    )
    (comp (ref "S1")
      (value "5x5mm Button")
      (footprint "430182070816")
      (description "Switch")
      (fields
        (field (name "MANUFACTURER_PART_NUMBER") "430182050816")
        (field (name "MOUSER PART NUMBER") "710-430182050816")
      )
      (libsource (lib "*") (part "430182050816"))
    )
    (comp (ref "S2")
      (value "5x5mm Button")
      (footprint "430182070816")
      (description "Switch")
      (fields
        (field (name "MANUFACTURER_PART_NUMBER") "430182050816")
        (field (name "MOUSER PART NUMBER") "710-430182050816")
      )
      (libsource (lib "*") (part "430182050816"))
    )
  )
  (nets
    (net (code "1") (name "/ALERT") (class "Default")
      (node (ref "IC1") (pin "8") (pinfunction "IO15_8") (pintype "passive"))
      (node (ref "IC6") (pin "19") (pinfunction "ALERT_19") (pintype "passive"))
      (node (ref "R14") (pin "2") (pinfunction "2_2") (pintype "passive"))
    )
    (net (code "2") (name "/CAL") (class "Default")
      (node (ref "IC1") (pin "28") (pinfunction "IO35_28") (pintype "passive"))
      (node (ref "IC5") (pin "31") (pinfunction "CAL_31") (pintype "input"))
    )
    (net (code "3") (name "/CC1") (class "Default")
      (node (ref "IC6") (pin "1") (pinfunction "CC1DB_1") (pintype "passive"))
      (node (ref "IC6") (pin "2") (pinfunction "CC1_2") (pintype "passive"))
      (node (ref "J2") (pin "A5") (pinfunction "CC1_A5") (pintype "bidirectional"))
    )
    (net (code "4") (name "/CC2") (class "Default")
      (node (ref "IC6") (pin "4") (pinfunction "CC2_4") (pintype "passive"))
      (node (ref "IC6") (pin "5") (pinfunction "CC2DB_5") (pintype "passive"))
      (node (ref "J2") (pin "B5") (pinfunction "CC2_B5") (pintype "bidirectional"))
    )
    (net (code "5") (name "/CHARGE") (class "Default")
      (node (ref "IC1") (pin "12") (pinfunction "IO8_12") (pintype "passive"))
      (node (ref "IC2") (pin "6") (pinfunction "~{EN}_6") (pintype "passive"))
      (node (ref "R45") (pin "1") (pinfunction "1_1") (pintype "passive"))
    )
    (net (code "6") (name "/DN") (class "Default")
      (node (ref "IC1") (pin "13") (pinfunction "IO19_13") (pintype "passive"))
      (node (ref "J2") (pin "A7") (pinfunction "DN1_A7") (pintype "bidirectional"))
      (node (ref "J2") (pin "B7") (pinfunction "DN2_B7") (pintype "bidirectional"))
    )
    (net (code "7") (name "/DP") (class "Default")
      (node (ref "IC1") (pin "14") (pinfunction "IO20_14") (pintype "passive"))
      (node (ref "J2") (pin "A6") (pinfunction "DP1_A6") (pintype "bidirectional"))
      (node (ref "J2") (pin "B6") (pinfunction "DP2_B6") (pintype "bidirectional"))
    )
    (net (code "8") (name "/EN") (class "Default")
      (node (ref "C10") (pin "1") (pinfunction "1_1") (pintype "passive"))
      (node (ref "IC1") (pin "3") (pinfunction "EN_3") (pintype "passive"))
      (node (ref "R7") (pin "2") (pinfunction "2_2") (pintype "passive"))
      (node (ref "S2") (pin "2") (pinfunction "2_2") (pintype "passive"))
      (node (ref "S2") (pin "4") (pinfunction "4_4") (pintype "passive"))
    )
    (net (code "9") (name "/ENABLE") (class "Default")
      (node (ref "IC1") (pin "29") (pinfunction "IO36_29") (pintype "passive"))
      (node (ref "IC5") (pin "30") (pinfunction "ENABLE_30") (pintype "input"))
    )
    (net (code "10") (name "/GHA") (class "Default")
      (node (ref "IC5") (pin "6") (pinfunction "GHA_6") (pintype "output"))
      (node (ref "Q5") (pin "1") (pinfunction "G_1") (pintype "passive"))
    )
    (net (code "11") (name "/GHB") (class "Default")
      (node (ref "IC5") (pin "15") (pinfunction "GHB_15") (pintype "output"))
      (node (ref "Q6") (pin "1") (pinfunction "G_1") (pintype "passive"))
    )
    (net (code "12") (name "/GHC") (class "Default")
      (node (ref "IC5") (pin "16") (pinfunction "GHC_16") (pintype "output"))
      (node (ref "Q7") (pin "1") (pinfunction "G_1") (pintype "passive"))
    )
    (net (code "13") (name "/GLA") (class "Default")
      (node (ref "IC5") (pin "8") (pinfunction "GLA_8") (pintype "output"))
      (node (ref "Q8") (pin "1") (pinfunction "G_1") (pintype "passive"))
    )
    (net (code "14") (name "/GLB") (class "Default")
      (node (ref "IC5") (pin "13") (pinfunction "GLB_13") (pintype "output"))
      (node (ref "Q9") (pin "1") (pinfunction "G_1") (pintype "passive"))
    )
    (net (code "15") (name "/GLC") (class "Default")
      (node (ref "IC5") (pin "18") (pinfunction "GLC_18") (pintype "output"))
      (node (ref "Q10") (pin "1") (pinfunction "G_1") (pintype "passive"))
    )
    (net (code "16") (name "/INHA") (class "Default")
      (node (ref "IC1") (pin "17") (pinfunction "IO9_17") (pintype "passive"))
      (node (ref "IC5") (pin "34") (pinfunction "INHA_34") (pintype "input"))
    )
    (net (code "17") (name "/INHB") (class "Default")
      (node (ref "IC1") (pin "19") (pinfunction "IO11_19") (pintype "passive"))
      (node (ref "IC5") (pin "36") (pinfunction "INHB_36") (pintype "input"))
    )
    (net (code "18") (name "/INHC") (class "Default")
      (node (ref "IC1") (pin "21") (pinfunction "IO13_21") (pintype "passive"))
      (node (ref "IC5") (pin "38") (pinfunction "INHC_38") (pintype "input"))
    )
    (net (code "19") (name "/INLA") (class "Default")
      (node (ref "IC1") (pin "18") (pinfunction "IO10_18") (pintype "passive"))
      (node (ref "IC5") (pin "35") (pinfunction "INLA_35") (pintype "input"))
    )
    (net (code "20") (name "/INLB") (class "Default")
      (node (ref "IC1") (pin "20") (pinfunction "IO12_20") (pintype "passive"))
      (node (ref "IC5") (pin "37") (pinfunction "INLB_37") (pintype "input"))
    )
    (net (code "21") (name "/INLC") (class "Default")
      (node (ref "IC1") (pin "23") (pinfunction "IO21_23") (pintype "passive"))
      (node (ref "IC5") (pin "39") (pinfunction "INLC_39") (pintype "input"))
    )
    (net (code "22") (name "/IO0") (class "Default")
      (node (ref "C6") (pin "2") (pinfunction "2_2") (pintype "passive"))
      (node (ref "IC1") (pin "27") (pinfunction "IO0_27") (pintype "passive"))
      (node (ref "R2") (pin "2") (pinfunction "2_2") (pintype "passive"))
      (node (ref "S1") (pin "1") (pinfunction "1_1") (pintype "passive"))
      (node (ref "S1") (pin "3") (pinfunction "3_3") (pintype "passive"))
    )
    (net (code "23") (name "/LEDC") (class "Default")
      (node (ref "IC1") (pin "5") (pinfunction "IO5_5") (pintype "passive"))
      (node (ref "IC8") (pin "5") (pinfunction "CIN_5") (pintype "passive"))
    )
    (net (code "24") (name "/LEDD") (class "Default")
      (node (ref "IC1") (pin "4") (pinfunction "IO4_4") (pintype "passive"))
      (node (ref "IC8") (pin "4") (pinfunction "DIN_4") (pintype "passive"))
    )
    (net (code "25") (name "/MISO_DRV") (class "Default")
      (node (ref "IC1") (pin "33") (pinfunction "IO40_33") (pintype "passive"))
      (node (ref "IC5") (pin "26") (pinfunction "SDO_26") (pintype "passive"))
    )
    (net (code "26") (name "/MOSI_DRV") (class "Default")
      (node (ref "IC1") (pin "32") (pinfunction "IO39_32") (pintype "passive"))
      (node (ref "IC5") (pin "27") (pinfunction "SDI_27") (pintype "input"))
    )
    (net (code "27") (name "/NFAULT") (class "Default")
      (node (ref "IC1") (pin "6") (pinfunction "IO6_6") (pintype "passive"))
      (node (ref "IC5") (pin "25") (pinfunction "NFAULT_25") (pintype "passive"))
      (node (ref "R25") (pin "2") (pinfunction "2_2") (pintype "passive"))
    )
    (net (code "28") (name "/PWM_Servo") (class "Default")
      (node (ref "IC1") (pin "25") (pinfunction "IO48_25") (pintype "passive"))
    )
    (net (code "29") (name "/RESET") (class "Default")
      (node (ref "IC1") (pin "15") (pinfunction "IO3_15") (pintype "passive"))
      (node (ref "IC6") (pin "6") (pinfunction "RESET_6") (pintype "passive"))
      (node (ref "R26") (pin "2") (pinfunction "2_2") (pintype "passive"))
    )
    (net (code "30") (name "/RXD") (class "Default")
      (node (ref "IC1") (pin "36") (pinfunction "RXD0_36") (pintype "passive"))
    )
    (net (code "31") (name "/SCL") (class "Default")
      (node (ref "IC1") (pin "10") (pinfunction "IO17_10") (pintype "passive"))
      (node (ref "IC6") (pin "7") (pinfunction "SCL_7") (pintype "passive"))
      (node (ref "R9") (pin "2") (pinfunction "2_2") (pintype "passive"))
    )
    (net (code "32") (name "/SCLK") (class "Default")
      (node (ref "IC1") (pin "31") (pinfunction "IO38_31") (pintype "passive"))
      (node (ref "IC5") (pin "28") (pinfunction "SCLK_28") (pintype "input"))
    )
    (net (code "33") (name "/SDA") (class "Default")
      (node (ref "IC1") (pin "9") (pinfunction "IO16_9") (pintype "passive"))
      (node (ref "IC6") (pin "8") (pinfunction "SDA_8") (pintype "passive"))
      (node (ref "R11") (pin "2") (pinfunction "2_2") (pintype "passive"))
    )
    (net (code "34") (name "/SHA") (class "Default")
      (node (ref "IC5") (pin "7") (pinfunction "SHA_7") (pintype "input"))
      (node (ref "Q5") (pin "3") (pinfunction "S_3") (pintype "passive"))
      (node (ref "Q8") (pin "2") (pinfunction "D_2") (pintype "passive"))
    )
    (net (code "35") (name "/SHB") (class "Default")
      (node (ref "IC5") (pin "14") (pinfunction "SHB_14") (pintype "input"))
      (node (ref "Q6") (pin "3") (pinfunction "S_3") (pintype "passive"))
      (node (ref "Q9") (pin "2") (pinfunction "D_2") (pintype "passive"))
    )
    (net (code "36") (name "/SHC") (class "Default")
      (node (ref "IC5") (pin "17") (pinfunction "SHC_17") (pintype "input"))
      (node (ref "Q10") (pin "2") (pinfunction "D_2") (pintype "passive"))
      (node (ref "Q7") (pin "3") (pinfunction "S_3") (pintype "passive"))
    )
    (net (code "37") (name "/SOA") (class "Default")
      (node (ref "IC1") (pin "34") (pinfunction "IO41_34") (pintype "passive"))
      (node (ref "IC5") (pin "23") (pinfunction "SOA_23") (pintype "output"))
    )
    (net (code "38") (name "/SOB") (class "Default")
      (node (ref "IC1") (pin "35") (pinfunction "IO42_35") (pintype "passive"))
      (node (ref "IC5") (pin "22") (pinfunction "SOB_22") (pintype "output"))
    )
    (net (code "39") (name "/SOC") (class "Default")
      (node (ref "IC1") (pin "38") (pinfunction "IO2_38") (pintype "passive"))
      (node (ref "IC5") (pin "21") (pinfunction "SOC_21") (pintype "output"))
    )
    (net (code "40") (name "/SPA") (class "Default")
      (node (ref "IC5") (pin "9") (pinfunction "SPA_9") (pintype "input"))
      (node (ref "Q8") (pin "3") (pinfunction "S_3") (pintype "passive"))
      (node (ref "R27") (pin "2") (pinfunction "2_2") (pintype "passive"))
    )
    (net (code "41") (name "/SPB") (class "Default")
      (node (ref "IC5") (pin "12") (pinfunction "SPB_12") (pintype "input"))
      (node (ref "Q9") (pin "3") (pinfunction "S_3") (pintype "passive"))
      (node (ref "R28") (pin "2") (pinfunction "2_2") (pintype "passive"))
    )
    (net (code "42") (name "/SPC") (class "Default")
      (node (ref "IC5") (pin "19") (pinfunction "SPC_19") (pintype "input"))
      (node (ref "Q10") (pin "3") (pinfunction "S_3") (pintype "passive"))
      (node (ref "R29") (pin "2") (pinfunction "2_2") (pintype "passive"))
    )
    (net (code "43") (name "/SS") (class "Default")
      (node (ref "IC1") (pin "30") (pinfunction "IO37_30") (pintype "passive"))
      (node (ref "IC5") (pin "29") (pinfunction "NSCS_29") (pintype "input"))
      (node (ref "R46") (pin "2") (pinfunction "2_2") (pintype "passive"))
    )
    (net (code "44") (name "/ST") (class "Default")
      (node (ref "IC1") (pin "7") (pinfunction "IO7_7") (pintype "passive"))
      (node (ref "IC4") (pin "9") (pinfunction "ST_9") (pintype "passive"))
      (node (ref "R15") (pin "1") (pinfunction "1_1") (pintype "passive"))
    )
    (net (code "45") (name "/TXD") (class "Default")
      (node (ref "IC1") (pin "37") (pinfunction "TXD0_37") (pintype "passive"))
    )
    (net (code "46") (name "/VBATADC") (class "Default")
      (node (ref "C41") (pin "2") (pinfunction "2_2") (pintype "passive"))
      (node (ref "IC1") (pin "11") (pinfunction "IO18_11") (pintype "passive"))
      (node (ref "R43") (pin "1") (pinfunction "1_1") (pintype "passive"))
      (node (ref "R44") (pin "2") (pinfunction "2_2") (pintype "passive"))
    )
    (net (code "47") (name "/VBUSADC") (class "Default")
      (node (ref "C36") (pin "2") (pinfunction "2_2") (pintype "passive"))
      (node (ref "IC1") (pin "22") (pinfunction "IO14_22") (pintype "passive"))
      (node (ref "R37") (pin "1") (pinfunction "1_1") (pintype "passive"))
      (node (ref "R38") (pin "2") (pinfunction "2_2") (pintype "passive"))
    )
    (net (code "48") (name "3V3") (class "Default")
      (node (ref "C1") (pin "1") (pinfunction "1_1") (pintype "passive"))
      (node (ref "C2") (pin "1") (pinfunction "1_1") (pintype "passive"))
      (node (ref "C3") (pin "2") (pinfunction "2_2") (pintype "passive"))
      (node (ref "C35") (pin "2") (pinfunction "2_2") (pintype "passive"))
      (node (ref "C4") (pin "2") (pinfunction "2_2") (pintype "passive"))
      (node (ref "IC1") (pin "2") (pinfunction "3V3_2") (pintype "passive"))
      (node (ref "IC5") (pin "24") (pinfunction "VREF_24") (pintype "power_in"))
      (node (ref "IC5") (pin "33") (pinfunction "DVDD_33") (pintype "power_in"))
      (node (ref "IC8") (pin "1") (pinfunction "VDD_1") (pintype "passive"))
      (node (ref "L1") (pin "1") (pinfunction "1_1") (pintype "passive"))
      (node (ref "R1") (pin "2") (pinfunction "2_2") (pintype "passive"))
      (node (ref "R11") (pin "1") (pinfunction "1_1") (pintype "passive"))
      (node (ref "R14") (pin "1") (pinfunction "1_1") (pintype "passive"))
      (node (ref "R15") (pin "2") (pinfunction "2_2") (pintype "passive"))
      (node (ref "R2") (pin "1") (pinfunction "1_1") (pintype "passive"))
      (node (ref "R25") (pin "1") (pinfunction "1_1") (pintype "passive"))
      (node (ref "R45") (pin "2") (pinfunction "2_2") (pintype "passive"))
      (node (ref "R46") (pin "1") (pinfunction "1_1") (pintype "passive"))
      (node (ref "R7") (pin "1") (pinfunction "1_1") (pintype "passive"))
      (node (ref "R9") (pin "1") (pinfunction "1_1") (pintype "passive"))
    )
    (net (code "49") (name "GND") (class "Default")
      (node (ref "C1") (pin "2") (pinfunction "2_2") (pintype "passive"))
      (node (ref "C10") (pin "2") (pinfunction "2_2") (pintype "passive"))
      (node (ref "C12") (pin "1") (pinfunction "1_1") (pintype "passive"))
      (node (ref "C13") (pin "1") (pinfunction "1_1") (pintype "passive"))
      (node (ref "C15") (pin "1") (pinfunction "1_1") (pintype "passive"))
      (node (ref "C16") (pin "1") (pinfunction "1_1") (pintype "passive"))
      (node (ref "C18") (pin "2") (pinfunction "2_2") (pintype "passive"))
      (node (ref "C2") (pin "2") (pinfunction "2_2") (pintype "passive"))
      (node (ref "C20") (pin "2") (pinfunction "2_2") (pintype "passive"))
      (node (ref "C21") (pin "2") (pinfunction "2_2") (pintype "passive"))
      (node (ref "C22") (pin "1") (pinfunction "1_1") (pintype "passive"))
      (node (ref "C23") (pin "2") (pinfunction "2_2") (pintype "passive"))
      (node (ref "C24") (pin "2") (pinfunction "2_2") (pintype "passive"))
      (node (ref "C25") (pin "2") (pinfunction "2_2") (pintype "passive"))
      (node (ref "C26") (pin "2") (pinfunction "2_2") (pintype "passive"))
      (node (ref "C27") (pin "2") (pinfunction "2_2") (pintype "passive"))
      (node (ref "C28") (pin "2") (pinfunction "2_2") (pintype "passive"))
      (node (ref "C29") (pin "1") (pinfunction "1_1") (pintype "passive"))
      (node (ref "C3") (pin "1") (pinfunction "1_1") (pintype "passive"))
      (node (ref "C30") (pin "1") (pinfunction "1_1") (pintype "passive"))
      (node (ref "C33") (pin "1") (pinfunction "1_1") (pintype "passive"))
      (node (ref "C34") (pin "1") (pinfunction "1_1") (pintype "passive"))
      (node (ref "C35") (pin "1") (pinfunction "1_1") (pintype "passive"))
      (node (ref "C36") (pin "1") (pinfunction "1_1") (pintype "passive"))
      (node (ref "C4") (pin "1") (pinfunction "1_1") (pintype "passive"))
      (node (ref "C41") (pin "1") (pinfunction "1_1") (pintype "passive"))
      (node (ref "C6") (pin "1") (pinfunction "1_1") (pintype "passive"))
      (node (ref "C7") (pin "2") (pinfunction "2_2") (pintype "passive"))
      (node (ref "C8") (pin "1") (pinfunction "1_1") (pintype "passive"))
      (node (ref "C9") (pin "1") (pinfunction "1_1") (pintype "passive"))
      (node (ref "D2") (pin "2") (pinfunction "A_2") (pintype "passive"))
      (node (ref "D3") (pin "2") (pinfunction "A_2") (pintype "passive"))
      (node (ref "IC1") (pin "1") (pinfunction "GND_1_1") (pintype "passive"))
      (node (ref "IC1") (pin "40") (pinfunction "GND_2_40") (pintype "passive"))
      (node (ref "IC1") (pin "41") (pinfunction "GND_3_41") (pintype "passive"))
      (node (ref "IC1") (pin "42") (pinfunction "GND_4_42") (pintype "passive"))
      (node (ref "IC1") (pin "43") (pinfunction "GND_5_43") (pintype "passive"))
      (node (ref "IC1") (pin "44") (pinfunction "GND_6_44") (pintype "passive"))
      (node (ref "IC1") (pin "45") (pinfunction "GND_7_45") (pintype "passive"))
      (node (ref "IC1") (pin "46") (pinfunction "GND_8_46") (pintype "passive"))
      (node (ref "IC1") (pin "47") (pinfunction "GND_9_47") (pintype "passive"))
      (node (ref "IC1") (pin "48") (pinfunction "GND_10_48") (pintype "passive"))
      (node (ref "IC1") (pin "49") (pinfunction "GND_11_49") (pintype "passive"))
      (node (ref "IC2") (pin "16") (pinfunction "PGND_16") (pintype "passive"))
      (node (ref "IC2") (pin "8") (pinfunction "AGND_8") (pintype "passive"))
      (node (ref "IC4") (pin "12") (pinfunction "GND_12") (pintype "passive"))
      (node (ref "IC4") (pin "3") (pinfunction "CP2_3") (pintype "passive"))
      (node (ref "IC4") (pin "4") (pinfunction "OV2_4") (pintype "passive"))
      (node (ref "IC4") (pin "5") (pinfunction "OV1_5") (pintype "passive"))
      (node (ref "IC5") (pin "10") (pinfunction "SNA_10") (pintype "input"))
      (node (ref "IC5") (pin "11") (pinfunction "SNB_11") (pintype "input"))
      (node (ref "IC5") (pin "20") (pinfunction "SNC_20") (pintype "input"))
      (node (ref "IC5") (pin "32") (pinfunction "AGND_32") (pintype "power_in"))
      (node (ref "IC5") (pin "40") (pinfunction "PGND_40") (pintype "power_in"))
      (node (ref "IC5") (pin "41") (pinfunction "EP_41") (pintype "power_in"))
      (node (ref "IC6") (pin "10") (pinfunction "GND_10") (pintype "passive"))
      (node (ref "IC6") (pin "12") (pinfunction "ADDR0_12") (pintype "passive"))
      (node (ref "IC6") (pin "13") (pinfunction "ADDR1_13") (pintype "passive"))
      (node (ref "IC6") (pin "22") (pinfunction "VSYS_22") (pintype "passive"))
      (node (ref "IC6") (pin "25") (pinfunction "EP_25") (pintype "passive"))
      (node (ref "IC8") (pin "6") (pinfunction "GND_6") (pintype "passive"))
      (node (ref "J2") (pin "A1_B12") (pinfunction "GND_A_A1_B12") (pintype "power_in"))
      (node (ref "J2") (pin "B1_A12") (pinfunction "GND_B_B1_A12") (pintype "power_in"))
      (node (ref "J2") (pin "SH1") (pinfunction "SHIELD_SH1") (pintype "passive"))
      (node (ref "J2") (pin "SH2") (pinfunction "SHIELD_SH2") (pintype "passive"))
      (node (ref "J2") (pin "SH3") (pinfunction "SHIELD_SH3") (pintype "passive"))
      (node (ref "J2") (pin "SH4") (pinfunction "SHIELD_SH4") (pintype "passive"))
      (node (ref "PS1") (pin "1") (pinfunction "GND_1") (pintype "power_in"))
      (node (ref "Q2") (pin "3") (pinfunction "S_3") (pintype "passive"))
      (node (ref "R16") (pin "1") (pinfunction "1_1") (pintype "passive"))
      (node (ref "R24") (pin "1") (pinfunction "1_1") (pintype "passive"))
      (node (ref "R26") (pin "1") (pinfunction "1_1") (pintype "passive"))
      (node (ref "R27") (pin "1") (pinfunction "1_1") (pintype "passive"))
      (node (ref "R28") (pin "1") (pinfunction "1_1") (pintype "passive"))
      (node (ref "R29") (pin "1") (pinfunction "1_1") (pintype "passive"))
      (node (ref "R38") (pin "1") (pinfunction "1_1") (pintype "passive"))
      (node (ref "R4") (pin "1") (pinfunction "1_1") (pintype "passive"))
      (node (ref "R44") (pin "1") (pinfunction "1_1") (pintype "passive"))
      (node (ref "R5") (pin "1") (pinfunction "1_1") (pintype "passive"))
      (node (ref "S1") (pin "2") (pinfunction "2_2") (pintype "passive"))
      (node (ref "S1") (pin "4") (pinfunction "4_4") (pintype "passive"))
      (node (ref "S2") (pin "1") (pinfunction "1_1") (pintype "passive"))
      (node (ref "S2") (pin "3") (pinfunction "3_3") (pintype "passive"))
    )
    (net (code "50") (name "Net-(C19-Pad2)") (class "Default")
      (node (ref "C19") (pin "2") (pinfunction "2_2") (pintype "passive"))
      (node (ref "R21") (pin "1") (pinfunction "1_1") (pintype "passive"))
    )
    (net (code "51") (name "Net-(D1-K)") (class "Default")
      (node (ref "C25") (pin "1") (pinfunction "1_1") (pintype "passive"))
      (node (ref "D1") (pin "1") (pinfunction "K_1") (pintype "passive"))
      (node (ref "R18") (pin "1") (pinfunction "1_1") (pintype "passive"))
      (node (ref "R22") (pin "2") (pinfunction "2_2") (pintype "passive"))
    )
    (net (code "52") (name "Net-(D3-K)") (class "Default")
      (node (ref "C19") (pin "1") (pinfunction "1_1") (pintype "passive"))
      (node (ref "D3") (pin "1") (pinfunction "K_1") (pintype "passive"))
      (node (ref "Q4") (pin "2") (pinfunction "D_2") (pintype "passive"))
      (node (ref "R20") (pin "2") (pinfunction "2_2") (pintype "passive"))
      (node (ref "R33") (pin "2") (pinfunction "2_2") (pintype "passive"))
    )
    (net (code "53") (name "Net-(IC2-BST)") (class "Default")
      (node (ref "C11") (pin "1") (pinfunction "1_1") (pintype "passive"))
      (node (ref "IC2") (pin "15") (pinfunction "BST_15") (pintype "passive"))
    )
    (net (code "54") (name "Net-(IC2-CSP)") (class "Default")
      (node (ref "IC2") (pin "10") (pinfunction "CSP_10") (pintype "passive"))
      (node (ref "L2") (pin "1") (pinfunction "1_1") (pintype "passive"))
      (node (ref "R6") (pin "1") (pinfunction "1_1") (pintype "passive"))
    )
    (net (code "55") (name "Net-(IC2-NTC)") (class "Default")
      (node (ref "IC2") (pin "13") (pinfunction "NTC_13") (pintype "passive"))
      (node (ref "R3") (pin "1") (pinfunction "1_1") (pintype "passive"))
      (node (ref "R4") (pin "2") (pinfunction "2_2") (pintype "passive"))
    )
    (net (code "56") (name "Net-(IC2-SW)") (class "Default")
      (node (ref "C11") (pin "2") (pinfunction "2_2") (pintype "passive"))
      (node (ref "IC2") (pin "1") (pinfunction "SW_1") (pintype "passive"))
      (node (ref "L2") (pin "2") (pinfunction "2_2") (pintype "passive"))
    )
    (net (code "57") (name "Net-(IC2-TMR)") (class "Default")
      (node (ref "C7") (pin "1") (pinfunction "1_1") (pintype "passive"))
      (node (ref "IC2") (pin "14") (pinfunction "TMR_14") (pintype "passive"))
    )
    (net (code "58") (name "Net-(IC2-VCC)") (class "Default")
      (node (ref "C9") (pin "2") (pinfunction "2_2") (pintype "passive"))
      (node (ref "IC2") (pin "3") (pinfunction "VCC_3") (pintype "passive"))
      (node (ref "R3") (pin "2") (pinfunction "2_2") (pintype "passive"))
    )
    (net (code "59") (name "Net-(IC2-VIN)") (class "Default")
      (node (ref "C12") (pin "2") (pinfunction "2_2") (pintype "passive"))
      (node (ref "C13") (pin "2") (pinfunction "2_2") (pintype "passive"))
      (node (ref "IC2") (pin "2") (pinfunction "VIN_2") (pintype "passive"))
      (node (ref "LED1") (pin "2") (pinfunction "A_2") (pintype "passive"))
      (node (ref "R30") (pin "2") (pinfunction "2_2") (pintype "passive"))
    )
    (net (code "60") (name "Net-(IC2-~{CHGOK})") (class "Default")
      (node (ref "IC2") (pin "11") (pinfunction "~{CHGOK}_11") (pintype "passive"))
      (node (ref "R8") (pin "1") (pinfunction "1_1") (pintype "passive"))
    )
    (net (code "61") (name "Net-(IC3-CO)") (class "Default")
      (node (ref "IC3") (pin "3") (pinfunction "CO_3") (pintype "passive"))
      (node (ref "Q2") (pin "1") (pinfunction "G_1") (pintype "passive"))
    )
    (net (code "62") (name "Net-(IC3-CTL)") (class "Default")
      (node (ref "IC3") (pin "1") (pinfunction "CTL_1") (pintype "passive"))
      (node (ref "R12") (pin "1") (pinfunction "1_1") (pintype "passive"))
    )
    (net (code "63") (name "Net-(IC3-DO)") (class "Default")
      (node (ref "IC3") (pin "4") (pinfunction "DO_4") (pintype "passive"))
      (node (ref "Q1") (pin "1") (pinfunction "G_1") (pintype "passive"))
    )
    (net (code "64") (name "Net-(IC3-EP)") (class "Default")
      (node (ref "C14") (pin "2") (pinfunction "2_2") (pintype "passive"))
      (node (ref "IC3") (pin "8") (pinfunction "VDD_8") (pintype "passive"))
      (node (ref "IC3") (pin "9") (pinfunction "EP_9") (pintype "passive"))
      (node (ref "R10") (pin "1") (pinfunction "1_1") (pintype "passive"))
    )
    (net (code "65") (name "Net-(IC3-VC)") (class "Default")
      (node (ref "C17") (pin "2") (pinfunction "2_2") (pintype "passive"))
      (node (ref "IC3") (pin "7") (pinfunction "VC_7") (pintype "passive"))
      (node (ref "R13") (pin "1") (pinfunction "1_1") (pintype "passive"))
    )
    (net (code "66") (name "Net-(IC3-VINI)") (class "Default")
      (node (ref "IC3") (pin "5") (pinfunction "VINI_5") (pintype "passive"))
      (node (ref "Q1") (pin "3") (pinfunction "S_3") (pintype "passive"))
      (node (ref "R17") (pin "1") (pinfunction "1_1") (pintype "passive"))
    )
    (net (code "67") (name "Net-(IC3-VM)") (class "Default")
      (node (ref "IC3") (pin "2") (pinfunction "VM_2") (pintype "passive"))
      (node (ref "R16") (pin "2") (pinfunction "2_2") (pintype "passive"))
    )
    (net (code "68") (name "Net-(IC4-ILIM)") (class "Default")
      (node (ref "IC4") (pin "10") (pinfunction "ILIM_10") (pintype "passive"))
      (node (ref "R24") (pin "2") (pinfunction "2_2") (pintype "passive"))
    )
    (net (code "69") (name "Net-(IC4-IN1)") (class "Default")
      (node (ref "C20") (pin "1") (pinfunction "1_1") (pintype "passive"))
      (node (ref "C21") (pin "1") (pinfunction "1_1") (pintype "passive"))
      (node (ref "IC4") (pin "6") (pinfunction "PR1_6") (pintype "passive"))
      (node (ref "IC4") (pin "7") (pinfunction "IN1_7") (pintype "passive"))
      (node (ref "R32") (pin "1") (pinfunction "1_1") (pintype "passive"))
    )
    (net (code "70") (name "Net-(IC4-IN2)") (class "Default")
      (node (ref "C27") (pin "1") (pinfunction "1_1") (pintype "passive"))
      (node (ref "C28") (pin "1") (pinfunction "1_1") (pintype "passive"))
      (node (ref "IC4") (pin "2") (pinfunction "IN2_2") (pintype "passive"))
      (node (ref "R35") (pin "2") (pinfunction "2_2") (pintype "passive"))
    )
    (net (code "71") (name "Net-(IC4-OUT_1)") (class "Default")
      (node (ref "C23") (pin "1") (pinfunction "1_1") (pintype "passive"))
      (node (ref "C24") (pin "1") (pinfunction "1_1") (pintype "passive"))
      (node (ref "IC4") (pin "1") (pinfunction "OUT_1_1") (pintype "passive"))
      (node (ref "IC4") (pin "8") (pinfunction "OUT_2_8") (pintype "passive"))
      (node (ref "R34") (pin "2") (pinfunction "2_2") (pintype "passive"))
    )
    (net (code "72") (name "Net-(IC4-SS)") (class "Default")
      (node (ref "C30") (pin "2") (pinfunction "2_2") (pintype "passive"))
      (node (ref "IC4") (pin "11") (pinfunction "SS_11") (pintype "passive"))
    )
    (net (code "73") (name "Net-(IC5-CPH)") (class "Default")
      (node (ref "C31") (pin "1") (pinfunction "1_1") (pintype "passive"))
      (node (ref "IC5") (pin "2") (pinfunction "CPH_2") (pintype "power_in"))
    )
    (net (code "74") (name "Net-(IC5-CPL)") (class "Default")
      (node (ref "C31") (pin "2") (pinfunction "2_2") (pintype "passive"))
      (node (ref "IC5") (pin "1") (pinfunction "CPL_1") (pintype "power_in"))
    )
    (net (code "75") (name "Net-(IC5-VCP)") (class "Default")
      (node (ref "C32") (pin "2") (pinfunction "2_2") (pintype "passive"))
      (node (ref "IC5") (pin "3") (pinfunction "VCP_3") (pintype "power_in"))
    )
    (net (code "76") (name "Net-(IC6-DISCH)") (class "Default")
      (node (ref "IC6") (pin "9") (pinfunction "DISCH_9") (pintype "passive"))
      (node (ref "R20") (pin "1") (pinfunction "1_1") (pintype "passive"))
    )
    (net (code "77") (name "Net-(IC6-VBUS_EN_SNK)") (class "Default")
      (node (ref "IC6") (pin "16") (pinfunction "VBUS_EN_SNK_16") (pintype "passive"))
      (node (ref "R23") (pin "1") (pinfunction "1_1") (pintype "passive"))
    )
    (net (code "78") (name "Net-(IC6-VBUS_VS_DISCH)") (class "Default")
      (node (ref "IC6") (pin "18") (pinfunction "VBUS_VS_DISCH_18") (pintype "passive"))
      (node (ref "R22") (pin "1") (pinfunction "1_1") (pintype "passive"))
    )
    (net (code "79") (name "Net-(IC6-VDD)") (class "Default")
      (node (ref "C22") (pin "2") (pinfunction "2_2") (pintype "passive"))
      (node (ref "IC6") (pin "24") (pinfunction "VDD_24") (pintype "passive"))
      (node (ref "Q3") (pin "3") (pinfunction "S_3") (pintype "passive"))
      (node (ref "Q4") (pin "3") (pinfunction "S_3") (pintype "passive"))
      (node (ref "R19") (pin "2") (pinfunction "2_2") (pintype "passive"))
    )
    (net (code "80") (name "Net-(IC6-VREG_1V2)") (class "Default")
      (node (ref "C29") (pin "2") (pinfunction "2_2") (pintype "passive"))
      (node (ref "IC6") (pin "21") (pinfunction "VREG_1V2_21") (pintype "passive"))
    )
    (net (code "81") (name "Net-(IC6-VREG_2V7)") (class "Default")
      (node (ref "C26") (pin "1") (pinfunction "1_1") (pintype "passive"))
      (node (ref "IC6") (pin "23") (pinfunction "VREG_2V7_23") (pintype "passive"))
    )
    (net (code "82") (name "Net-(IC7-CD)") (class "Default")
      (node (ref "C39") (pin "2") (pinfunction "2_2") (pintype "passive"))
      (node (ref "IC7") (pin "4") (pinfunction "CD_4") (pintype "passive"))
    )
    (net (code "83") (name "Net-(IC7-VC1)") (class "Default")
      (node (ref "C37") (pin "1") (pinfunction "1_1") (pintype "passive"))
      (node (ref "C38") (pin "2") (pinfunction "2_2") (pintype "passive"))
      (node (ref "IC7") (pin "2") (pinfunction "VC1_2") (pintype "passive"))
      (node (ref "R41") (pin "1") (pinfunction "1_1") (pintype "passive"))
    )
    (net (code "84") (name "Net-(IC7-VC1_CB)") (class "Default")
      (node (ref "IC7") (pin "3") (pinfunction "VC1_CB_3") (pintype "passive"))
      (node (ref "R42") (pin "1") (pinfunction "1_1") (pintype "passive"))
    )
    (net (code "85") (name "Net-(IC7-VC2)") (class "Default")
      (node (ref "C37") (pin "2") (pinfunction "2_2") (pintype "passive"))
      (node (ref "IC7") (pin "1") (pinfunction "VC2_1") (pintype "passive"))
      (node (ref "R39") (pin "1") (pinfunction "1_1") (pintype "passive"))
    )
    (net (code "86") (name "Net-(IC7-VDD)") (class "Default")
      (node (ref "C40") (pin "2") (pinfunction "2_2") (pintype "passive"))
      (node (ref "IC7") (pin "7") (pinfunction "VDD_7") (pintype "passive"))
      (node (ref "R40") (pin "2") (pinfunction "2_2") (pintype "passive"))
    )
    (net (code "87") (name "Net-(LED1-K)") (class "Default")
      (node (ref "LED1") (pin "1") (pinfunction "K_1") (pintype "passive"))
      (node (ref "R8") (pin "2") (pinfunction "2_2") (pintype "passive"))
    )
    (net (code "88") (name "Net-(PS1-CB)") (class "Default")
      (node (ref "C5") (pin "1") (pinfunction "1_1") (pintype "passive"))
      (node (ref "PS1") (pin "6") (pinfunction "CB_6") (pintype "power_in"))
    )
    (net (code "89") (name "Net-(PS1-FB)") (class "Default")
      (node (ref "PS1") (pin "4") (pinfunction "FB_4") (pintype "input"))
      (node (ref "R1") (pin "1") (pinfunction "1_1") (pintype "passive"))
      (node (ref "R5") (pin "2") (pinfunction "2_2") (pintype "passive"))
    )
    (net (code "90") (name "Net-(PS1-SW)") (class "Default")
      (node (ref "C5") (pin "2") (pinfunction "2_2") (pintype "passive"))
      (node (ref "L1") (pin "2") (pinfunction "2_2") (pintype "passive"))
      (node (ref "PS1") (pin "2") (pinfunction "SW_2") (pintype "power_in"))
    )
    (net (code "91") (name "Net-(Q1-D)") (class "Default")
      (node (ref "Q1") (pin "2") (pinfunction "D_2") (pintype "passive"))
      (node (ref "Q2") (pin "2") (pinfunction "D_2") (pintype "passive"))
    )
    (net (code "92") (name "Net-(Q3-G)") (class "Default")
      (node (ref "Q3") (pin "1") (pinfunction "G_1") (pintype "passive"))
      (node (ref "Q4") (pin "1") (pinfunction "G_1") (pintype "passive"))
      (node (ref "R19") (pin "1") (pinfunction "1_1") (pintype "passive"))
      (node (ref "R21") (pin "2") (pinfunction "2_2") (pintype "passive"))
      (node (ref "R23") (pin "2") (pinfunction "2_2") (pintype "passive"))
    )
    (net (code "93") (name "VBAT+") (class "Default")
      (node (ref "C15") (pin "2") (pinfunction "2_2") (pintype "passive"))
      (node (ref "C16") (pin "2") (pinfunction "2_2") (pintype "passive"))
      (node (ref "IC2") (pin "9") (pinfunction "BATT_9") (pintype "passive"))
      (node (ref "J1") (pin "1") (pinfunction "1_1") (pintype "passive"))
      (node (ref "J3") (pin "1") (pinfunction "1_1") (pintype "passive"))
      (node (ref "R10") (pin "2") (pinfunction "2_2") (pintype "passive"))
      (node (ref "R12") (pin "2") (pinfunction "2_2") (pintype "passive"))
      (node (ref "R31") (pin "1") (pinfunction "1_1") (pintype "passive"))
      (node (ref "R39") (pin "2") (pinfunction "2_2") (pintype "passive"))
      (node (ref "R40") (pin "1") (pinfunction "1_1") (pintype "passive"))
      (node (ref "R43") (pin "2") (pinfunction "2_2") (pintype "passive"))
      (node (ref "R6") (pin "2") (pinfunction "2_2") (pintype "passive"))
    )
    (net (code "94") (name "VBAT-") (class "Default")
      (node (ref "C14") (pin "1") (pinfunction "1_1") (pintype "passive"))
      (node (ref "C17") (pin "1") (pinfunction "1_1") (pintype "passive"))
      (node (ref "C38") (pin "1") (pinfunction "1_1") (pintype "passive"))
      (node (ref "C39") (pin "1") (pinfunction "1_1") (pintype "passive"))
      (node (ref "C40") (pin "1") (pinfunction "1_1") (pintype "passive"))
      (node (ref "IC3") (pin "6") (pinfunction "VSS_6") (pintype "passive"))
      (node (ref "IC7") (pin "5") (pinfunction "GND_1_5") (pintype "passive"))
      (node (ref "IC7") (pin "6") (pinfunction "~{CB_EN}_6") (pintype "passive"))
      (node (ref "IC7") (pin "9") (pinfunction "GND_2_9") (pintype "passive"))
      (node (ref "J1") (pin "3") (pinfunction "3_3") (pintype "passive"))
      (node (ref "J3") (pin "2") (pinfunction "2_2") (pintype "passive"))
      (node (ref "R17") (pin "2") (pinfunction "2_2") (pintype "passive"))
    )
    (net (code "95") (name "VBATJ") (class "Default")
      (node (ref "R31") (pin "2") (pinfunction "2_2") (pintype "passive"))
      (node (ref "R35") (pin "1") (pinfunction "1_1") (pintype "passive"))
      (node (ref "R36") (pin "1") (pinfunction "1_1") (pintype "passive"))
    )
    (net (code "96") (name "VBATM") (class "Default")
      (node (ref "J1") (pin "2") (pinfunction "2_2") (pintype "passive"))
      (node (ref "R13") (pin "2") (pinfunction "2_2") (pintype "passive"))
      (node (ref "R41") (pin "2") (pinfunction "2_2") (pintype "passive"))
      (node (ref "R42") (pin "2") (pinfunction "2_2") (pintype "passive"))
    )
    (net (code "97") (name "VBUS") (class "Default")
      (node (ref "C18") (pin "1") (pinfunction "1_1") (pintype "passive"))
      (node (ref "D1") (pin "2") (pinfunction "A_2") (pintype "passive"))
      (node (ref "D2") (pin "1") (pinfunction "K_1") (pintype "passive"))
      (node (ref "J2") (pin "A4_B9") (pinfunction "VBUS_A_A4_B9") (pintype "power_in"))
      (node (ref "J2") (pin "B4_A9") (pinfunction "VBUS_B_B4_A9") (pintype "power_in"))
      (node (ref "Q3") (pin "2") (pinfunction "D_2") (pintype "passive"))
      (node (ref "R18") (pin "2") (pinfunction "2_2") (pintype "passive"))
      (node (ref "R37") (pin "2") (pinfunction "2_2") (pintype "passive"))
    )
    (net (code "98") (name "VDRAIN") (class "Default")
      (node (ref "C32") (pin "1") (pinfunction "1_1") (pintype "passive"))
      (node (ref "C33") (pin "2") (pinfunction "2_2") (pintype "passive"))
      (node (ref "C34") (pin "2") (pinfunction "2_2") (pintype "passive"))
      (node (ref "IC5") (pin "4") (pinfunction "VM_4") (pintype "power_in"))
      (node (ref "IC5") (pin "5") (pinfunction "VDRAIN_5") (pintype "input"))
      (node (ref "Q5") (pin "2") (pinfunction "D_2") (pintype "passive"))
      (node (ref "Q6") (pin "2") (pinfunction "D_2") (pintype "passive"))
      (node (ref "Q7") (pin "2") (pinfunction "D_2") (pintype "passive"))
      (node (ref "R36") (pin "2") (pinfunction "2_2") (pintype "passive"))
    )
    (net (code "99") (name "VMCU") (class "Default")
      (node (ref "C8") (pin "2") (pinfunction "2_2") (pintype "passive"))
      (node (ref "PS1") (pin "3") (pinfunction "VIN_3") (pintype "power_in"))
      (node (ref "PS1") (pin "5") (pinfunction "EN_5") (pintype "input"))
      (node (ref "R34") (pin "1") (pinfunction "1_1") (pintype "passive"))
    )
    (net (code "100") (name "VSYS") (class "Default")
      (node (ref "R30") (pin "1") (pinfunction "1_1") (pintype "passive"))
      (node (ref "R32") (pin "2") (pinfunction "2_2") (pintype "passive"))
      (node (ref "R33") (pin "1") (pinfunction "1_1") (pintype "passive"))
    )
    (net (code "101") (name "unconnected-(IC1-IO1-Pad39)") (class "Default")
      (node (ref "IC1") (pin "39") (pinfunction "IO1_39") (pintype "passive"))
    )
    (net (code "102") (name "unconnected-(IC1-IO45-Pad26)") (class "Default")
      (node (ref "IC1") (pin "26") (pinfunction "IO45_26") (pintype "passive+no_connect"))
    )
    (net (code "103") (name "unconnected-(IC1-IO46-Pad16)") (class "Default")
      (node (ref "IC1") (pin "16") (pinfunction "IO46_16") (pintype "passive+no_connect"))
    )
    (net (code "104") (name "unconnected-(IC1-IO47-Pad24)") (class "Default")
      (node (ref "IC1") (pin "24") (pinfunction "IO47_24") (pintype "passive"))
    )
    (net (code "105") (name "unconnected-(IC2-CELL-Pad4)") (class "Default")
      (node (ref "IC2") (pin "4") (pinfunction "CELL_4") (pintype "passive+no_connect"))
    )
    (net (code "106") (name "unconnected-(IC2-NC-Pad7)") (class "Default")
      (node (ref "IC2") (pin "7") (pinfunction "NC_7") (pintype "passive+no_connect"))
    )
    (net (code "107") (name "unconnected-(IC2-SEL-Pad5)") (class "Default")
      (node (ref "IC2") (pin "5") (pinfunction "SEL_5") (pintype "passive+no_connect"))
    )
    (net (code "108") (name "unconnected-(IC2-~{ACOK}-Pad12)") (class "Default")
      (node (ref "IC2") (pin "12") (pinfunction "~{ACOK}_12") (pintype "passive+no_connect"))
    )
    (net (code "109") (name "unconnected-(IC6-ATTACH-Pad11)") (class "Default")
      (node (ref "IC6") (pin "11") (pinfunction "ATTACH_11") (pintype "passive+no_connect"))
    )
    (net (code "110") (name "unconnected-(IC6-A_B_SIDE-Pad17)") (class "Default")
      (node (ref "IC6") (pin "17") (pinfunction "A_B_SIDE_17") (pintype "passive+no_connect"))
    )
    (net (code "111") (name "unconnected-(IC6-GPIO-Pad15)") (class "Default")
      (node (ref "IC6") (pin "15") (pinfunction "GPIO_15") (pintype "passive+no_connect"))
    )
    (net (code "112") (name "unconnected-(IC6-NC-Pad3)") (class "Default")
      (node (ref "IC6") (pin "3") (pinfunction "NC_3") (pintype "passive+no_connect"))
    )
    (net (code "113") (name "unconnected-(IC6-POWER_OK2-Pad20)") (class "Default")
      (node (ref "IC6") (pin "20") (pinfunction "POWER_OK2_20") (pintype "passive+no_connect"))
    )
    (net (code "114") (name "unconnected-(IC6-POWER_OK3-Pad14)") (class "Default")
      (node (ref "IC6") (pin "14") (pinfunction "POWER_OK3_14") (pintype "passive+no_connect"))
    )
    (net (code "115") (name "unconnected-(IC7-OUT-Pad8)") (class "Default")
      (node (ref "IC7") (pin "8") (pinfunction "OUT_8") (pintype "passive+no_connect"))
    )
    (net (code "116") (name "unconnected-(IC8-COUT-Pad2)") (class "Default")
      (node (ref "IC8") (pin "2") (pinfunction "COUT_2") (pintype "passive+no_connect"))
    )
    (net (code "117") (name "unconnected-(IC8-DOUT-Pad3)") (class "Default")
      (node (ref "IC8") (pin "3") (pinfunction "DOUT_3") (pintype "passive+no_connect"))
    )
    (net (code "118") (name "unconnected-(J2-SBU1-PadA8)") (class "Default")
      (node (ref "J2") (pin "A8") (pinfunction "SBU1_A8") (pintype "bidirectional+no_connect"))
    )
    (net (code "119") (name "unconnected-(J2-SBU2-PadB8)") (class "Default")
      (node (ref "J2") (pin "B8") (pinfunction "SBU2_B8") (pintype "bidirectional+no_connect"))
    )
  )
)
